# MotherBoard.net
KiCad netlist of a schematic drawn in EAGLE
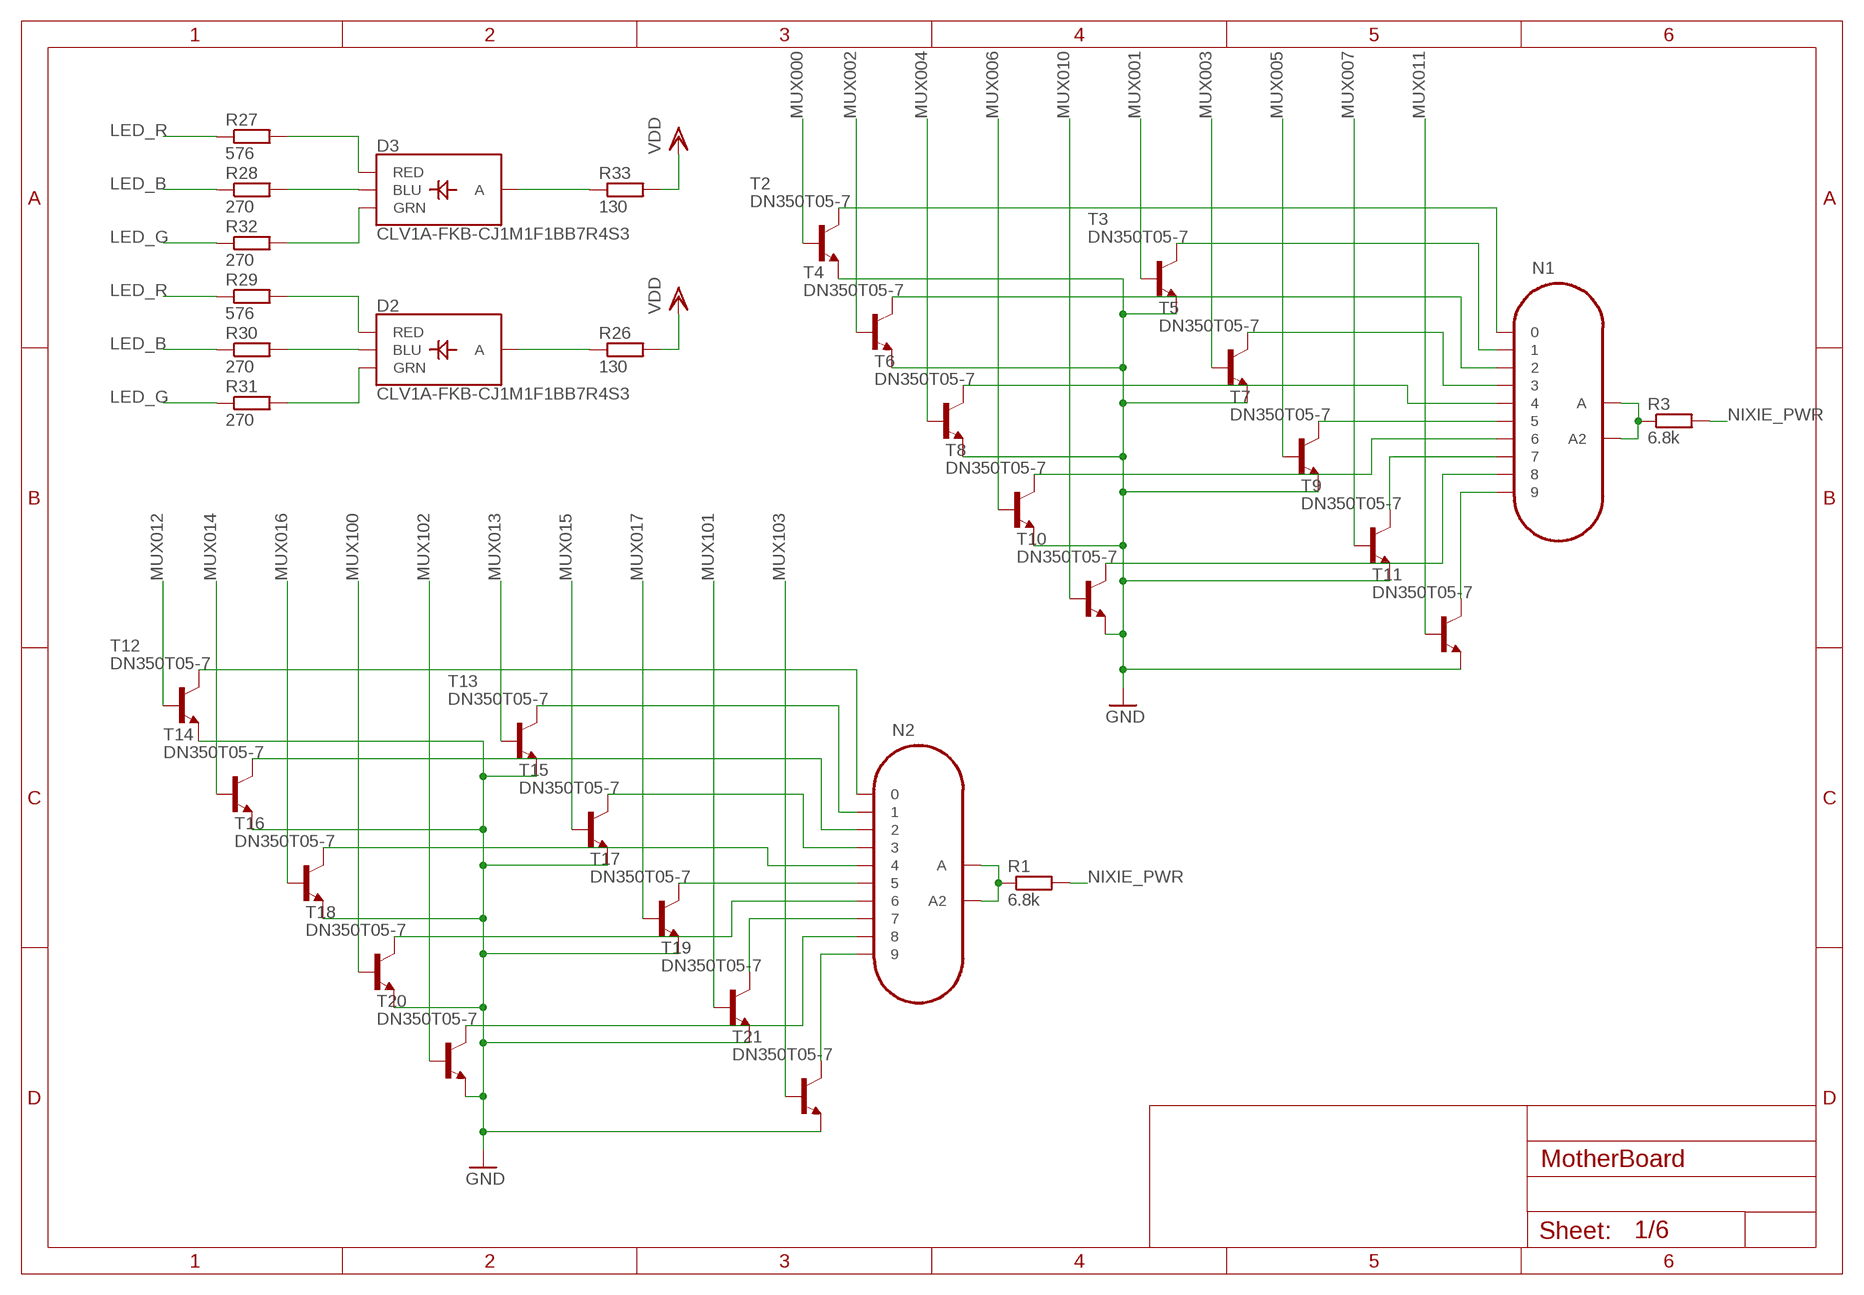
[diagram p0: schematic, sheet 1]
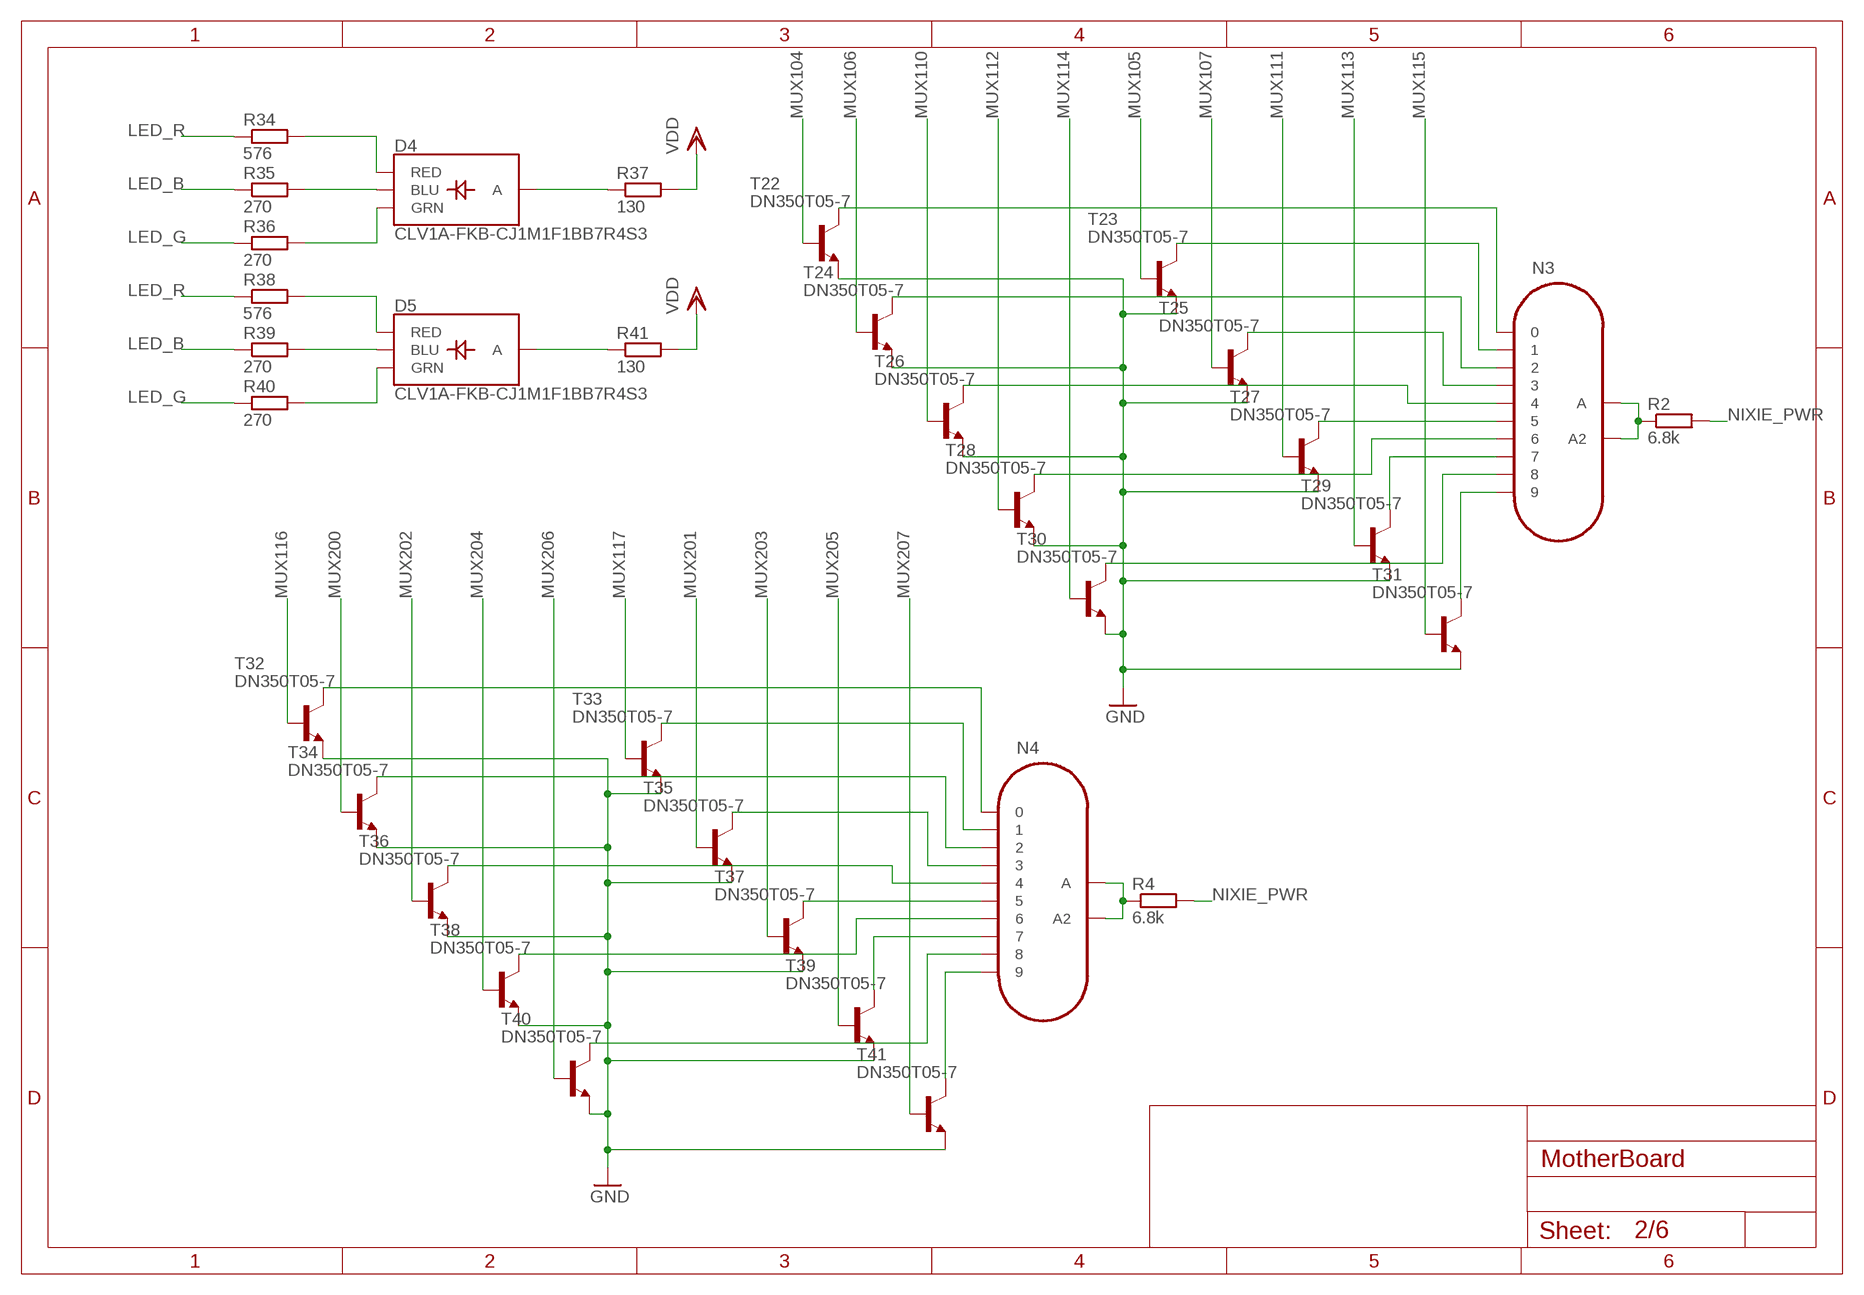
[diagram p1: schematic, sheet 2]
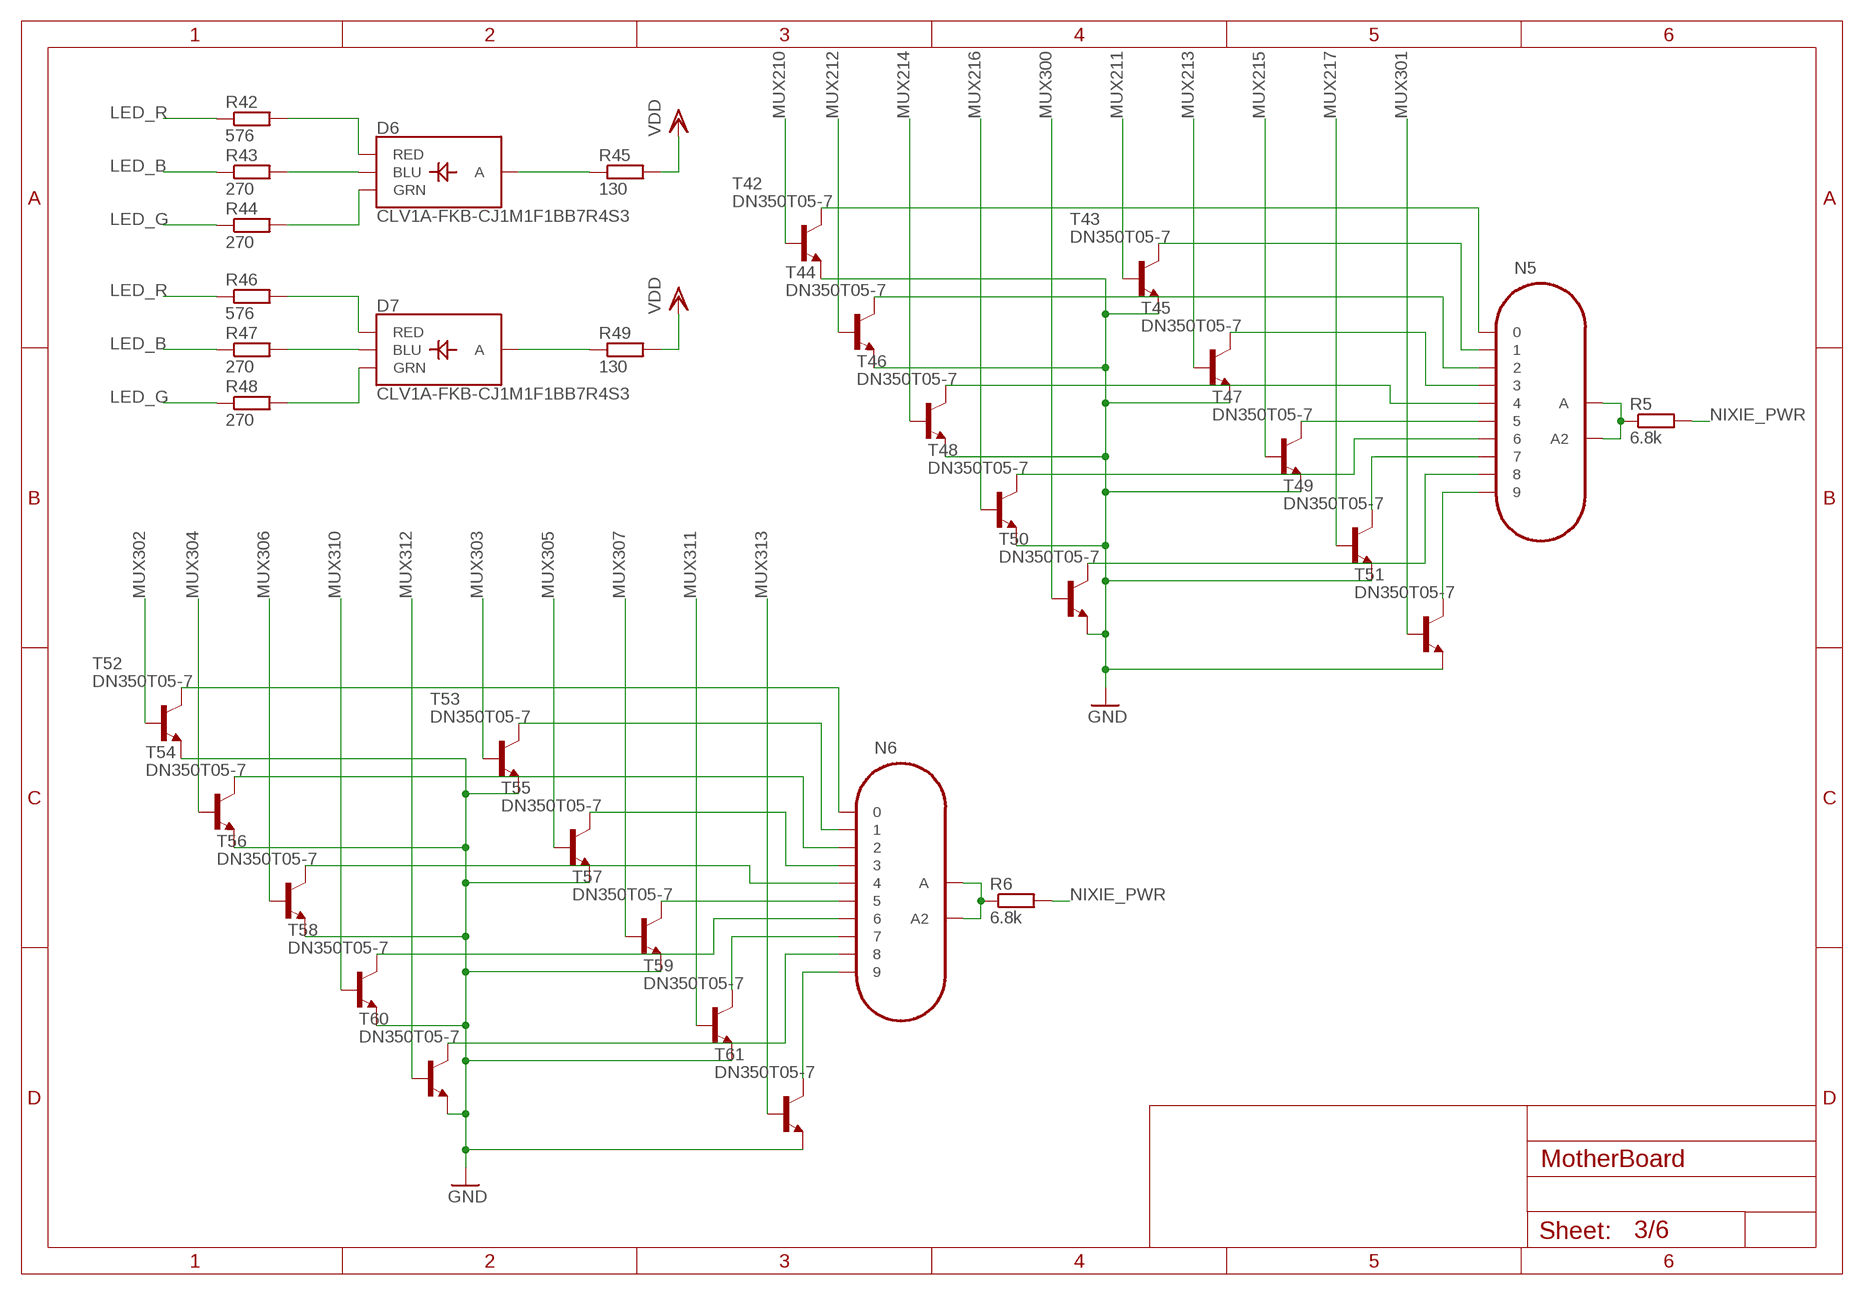
[diagram p2: schematic, sheet 3]
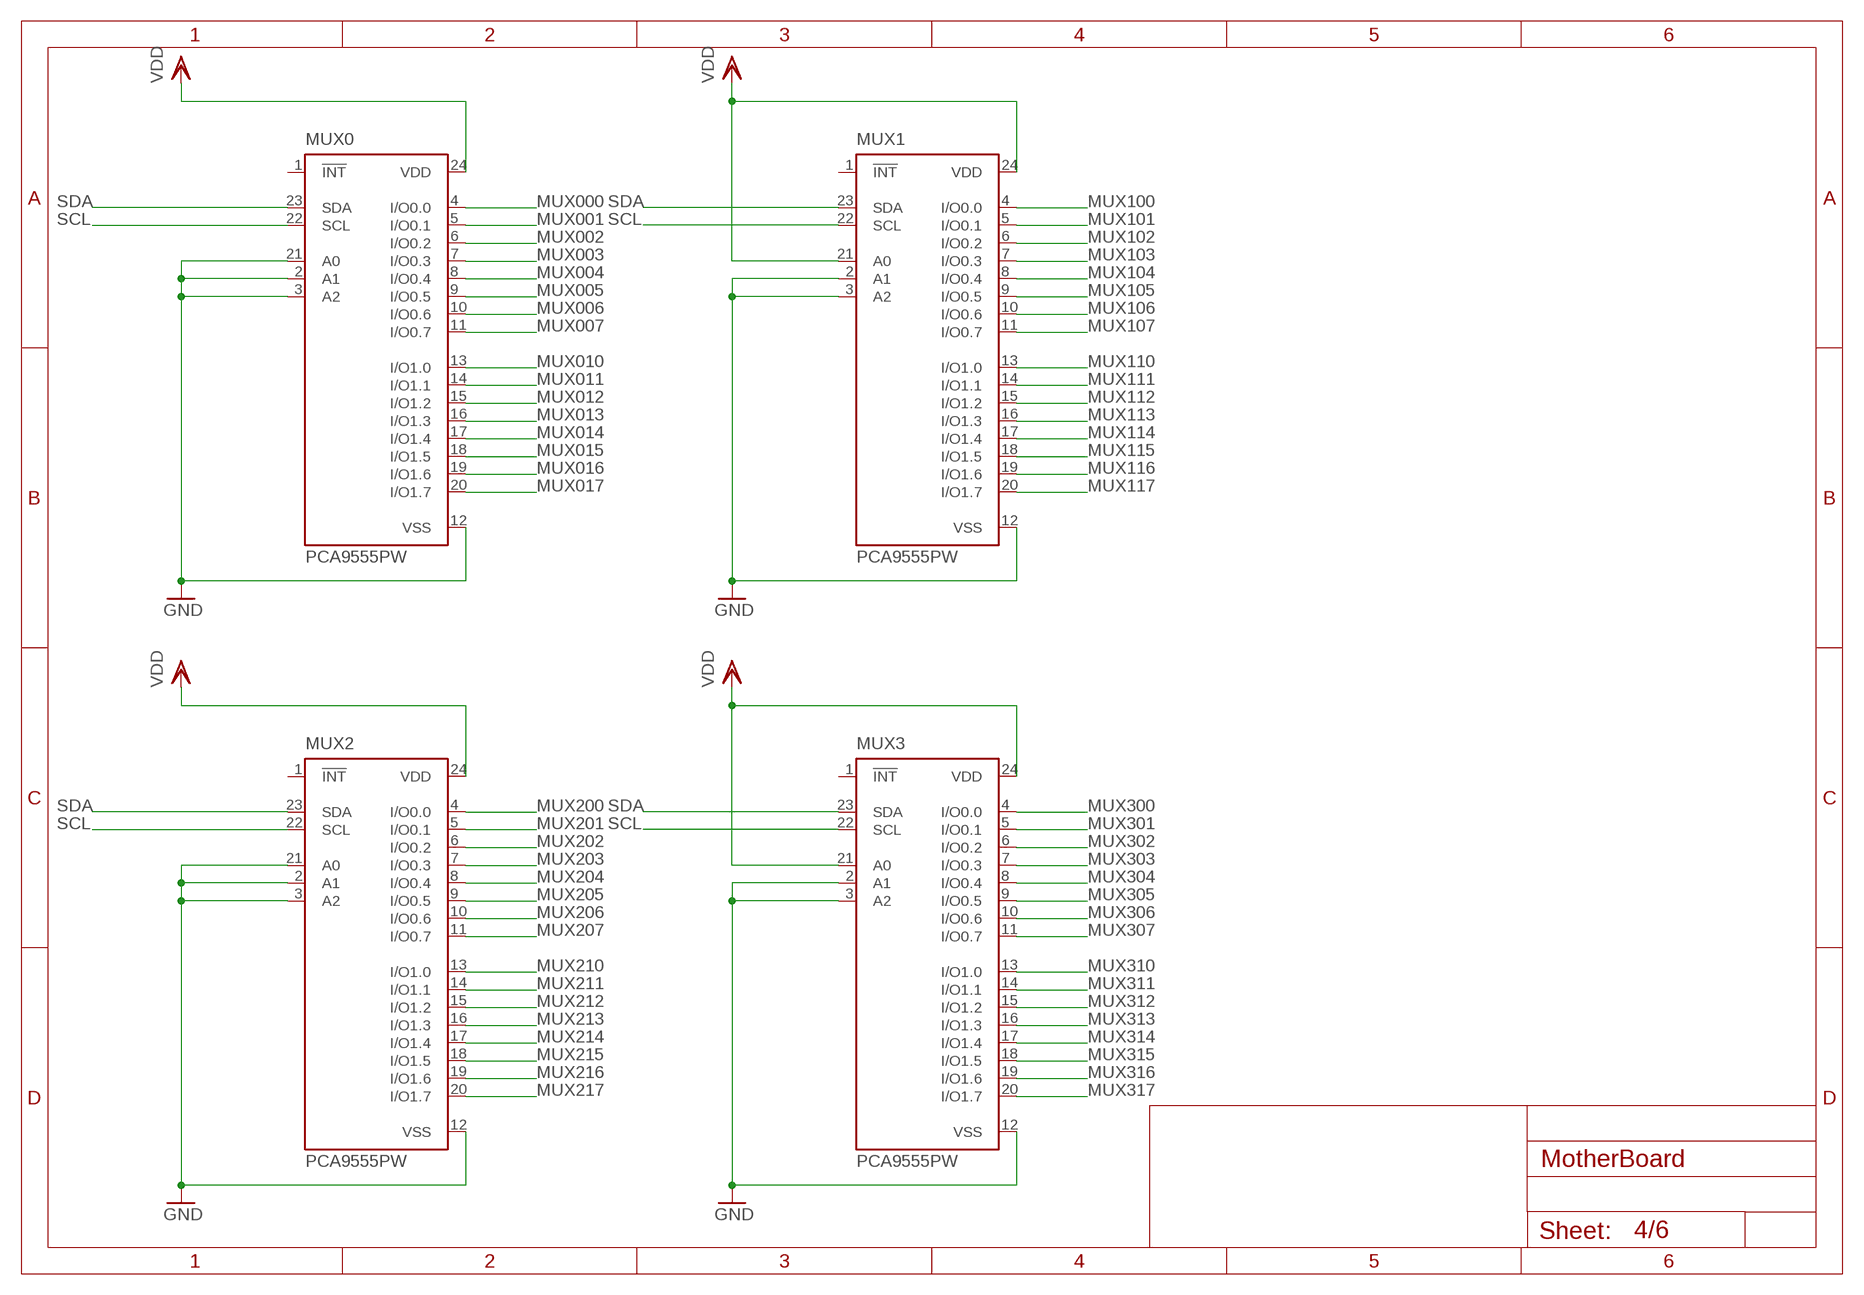
[diagram p3: schematic, sheet 4]
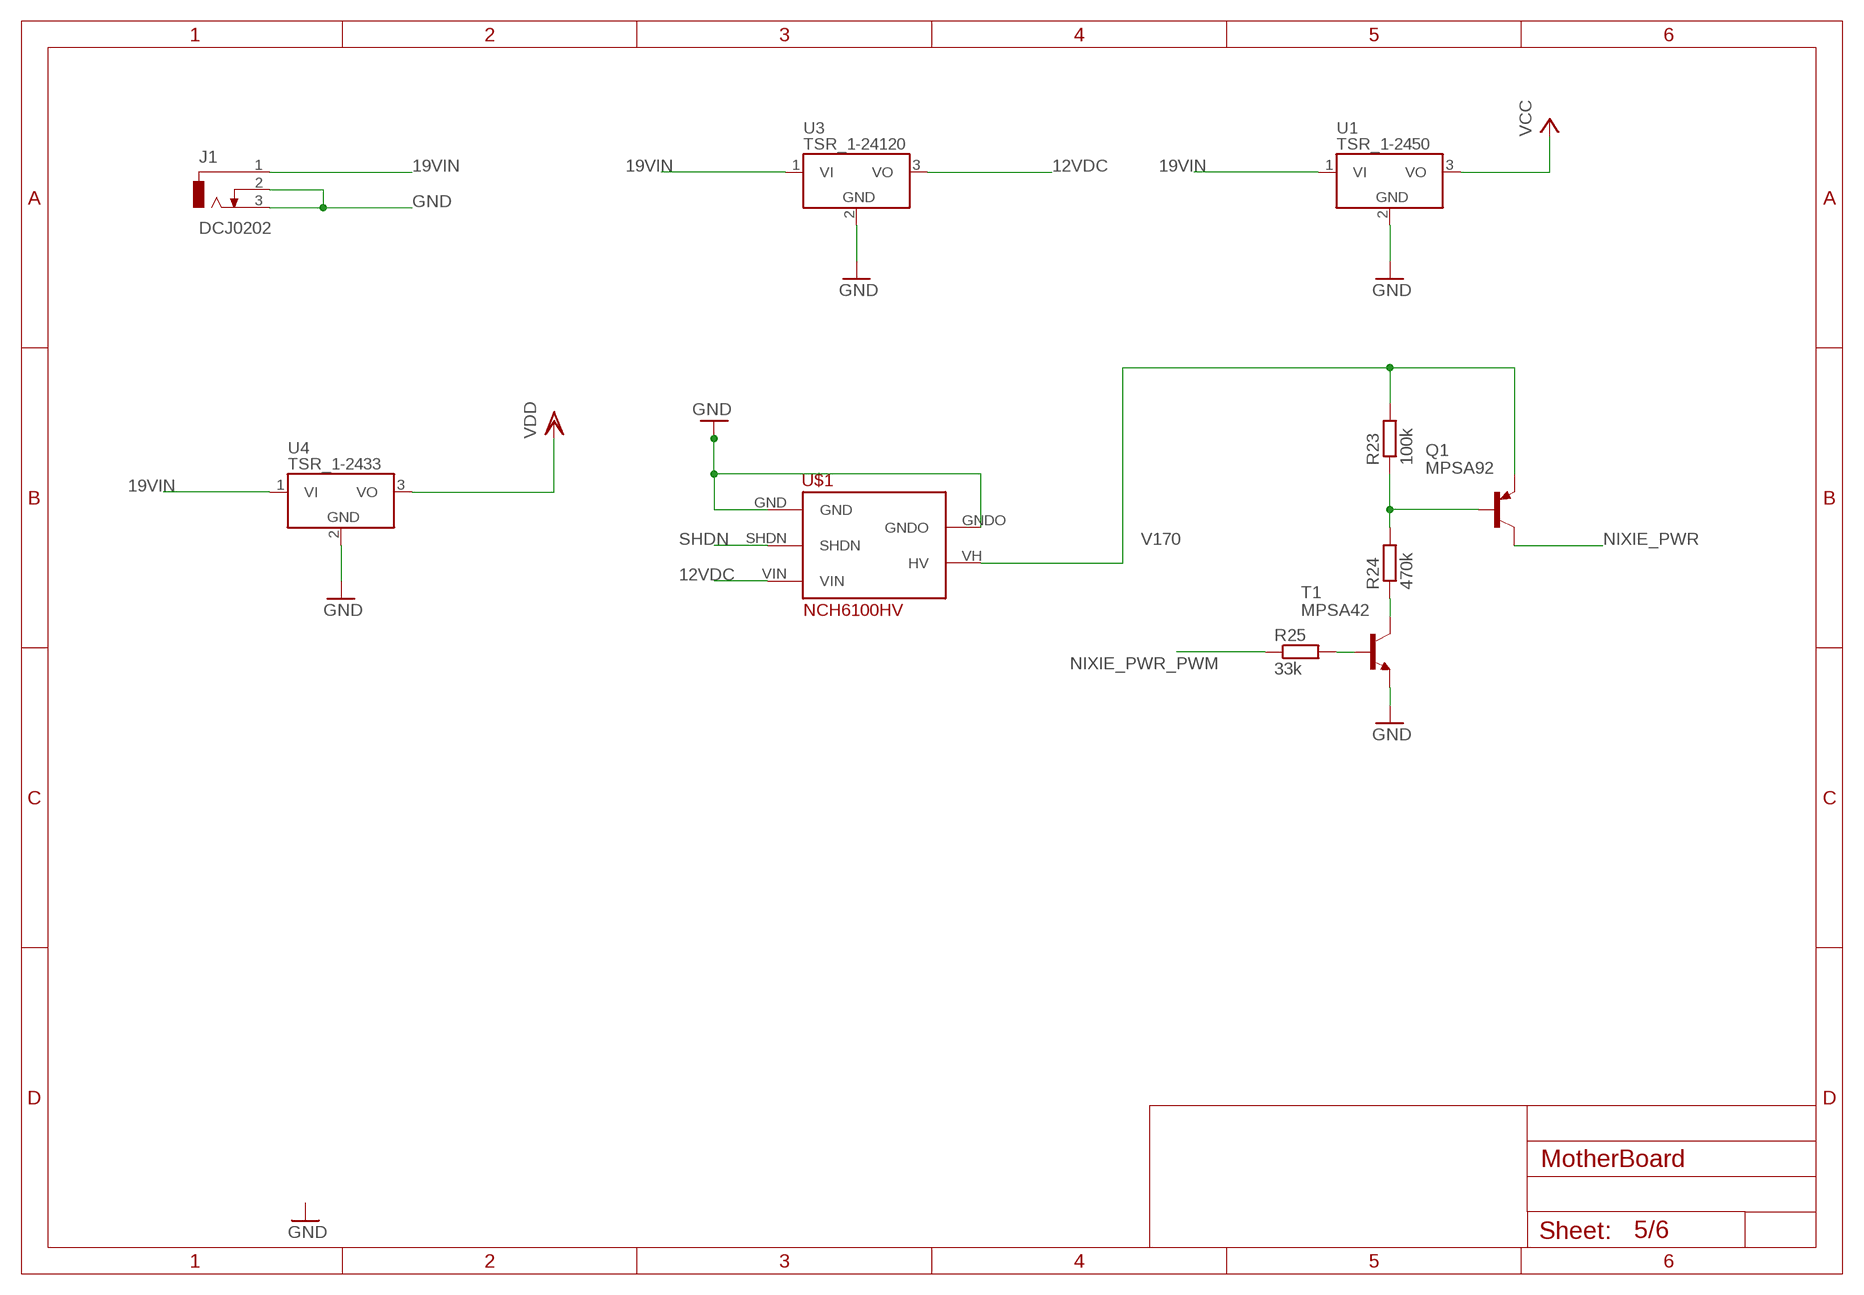
[diagram p4: schematic, sheet 5]
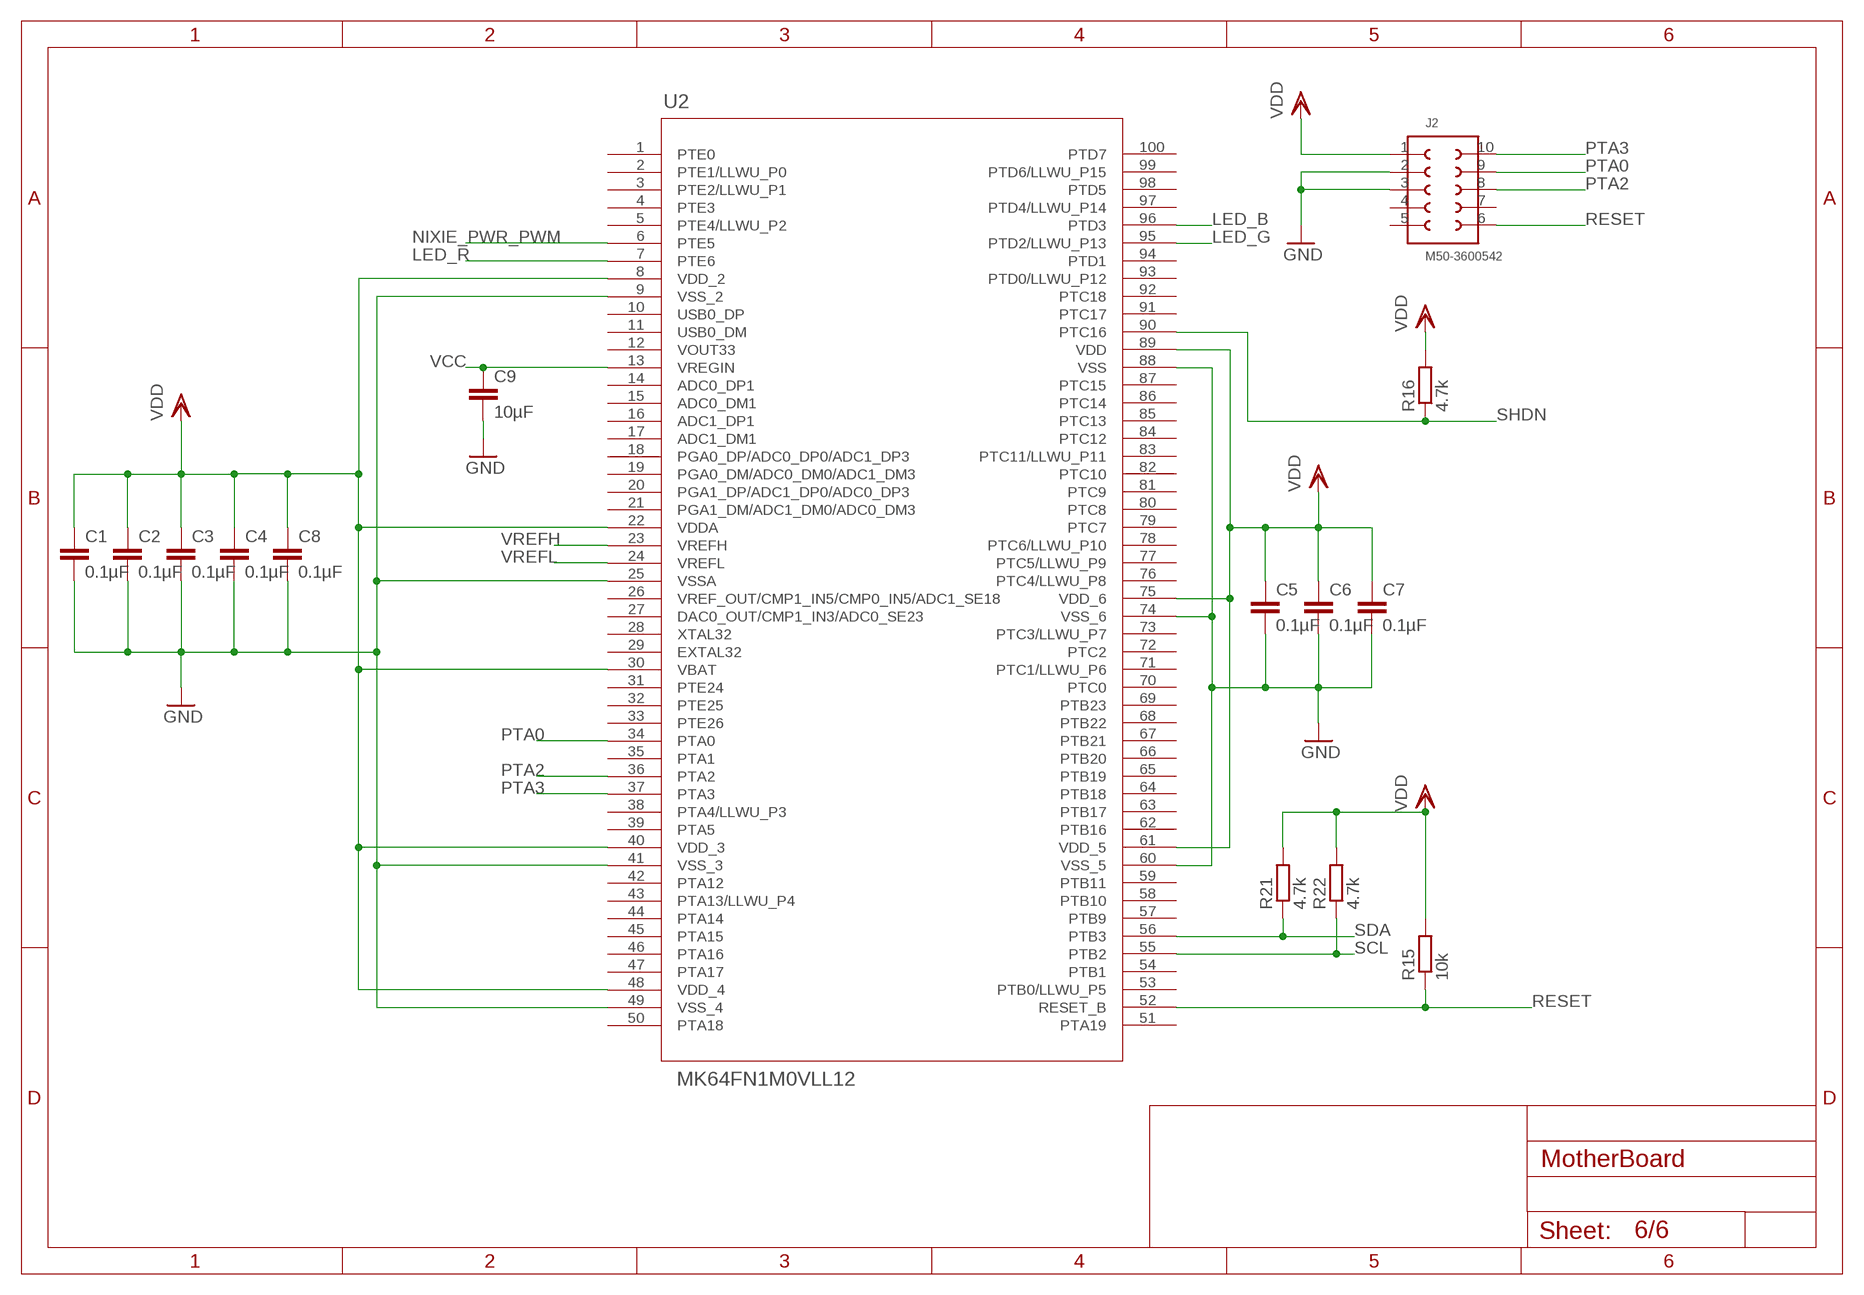
[diagram p5: schematic, sheet 6]

(export (version "E")
  (design (tool "Eeschema 10.0.6"))
  (components
    (comp (ref "C1")
      (value "0.1µF")
      (footprint "eagle-import:C0603")
      (libsource (lib "eagle-import") (part "C-EUC0603"))
    )
    (comp (ref "C2")
      (value "0.1µF")
      (footprint "eagle-import:C0603")
      (libsource (lib "eagle-import") (part "C-EUC0603"))
    )
    (comp (ref "C3")
      (value "0.1µF")
      (footprint "eagle-import:C0603")
      (libsource (lib "eagle-import") (part "C-EUC0603"))
    )
    (comp (ref "C4")
      (value "0.1µF")
      (footprint "eagle-import:C0603")
      (libsource (lib "eagle-import") (part "C-EUC0603"))
    )
    (comp (ref "C5")
      (value "0.1µF")
      (footprint "eagle-import:C0603")
      (libsource (lib "eagle-import") (part "C-EUC0603"))
    )
    (comp (ref "C6")
      (value "0.1µF")
      (footprint "eagle-import:C0603")
      (libsource (lib "eagle-import") (part "C-EUC0603"))
    )
    (comp (ref "C7")
      (value "0.1µF")
      (footprint "eagle-import:C0603")
      (libsource (lib "eagle-import") (part "C-EUC0603"))
    )
    (comp (ref "C8")
      (value "0.1µF")
      (footprint "eagle-import:C0603")
      (libsource (lib "eagle-import") (part "C-EUC0603"))
    )
    (comp (ref "C9")
      (value "10µF")
      (footprint "eagle-import:C0603")
      (libsource (lib "eagle-import") (part "C-EUC0603"))
    )
    (comp (ref "J2")
      (value "M50-3600542")
      (footprint "eagle-import:621X1021021")
      (libsource (lib "eagle-import") (part "621X1021021"))
    )
    (comp (ref "R15")
      (value "10k")
      (footprint "eagle-import:R0603")
      (libsource (lib "eagle-import") (part "R-EU_R0603"))
    )
    (comp (ref "R16")
      (value "4.7k")
      (footprint "eagle-import:R0603")
      (libsource (lib "eagle-import") (part "R-EU_R0603"))
    )
    (comp (ref "R21")
      (value "4.7k")
      (footprint "eagle-import:R0603")
      (libsource (lib "eagle-import") (part "R-EU_R0603"))
    )
    (comp (ref "R22")
      (value "4.7k")
      (footprint "eagle-import:R0603")
      (libsource (lib "eagle-import") (part "R-EU_R0603"))
    )
    (comp (ref "U2")
      (value "MK64FN1M0VLL12")
      (footprint "eagle-import:LQFP-100_14X14X1.7")
      (fields (field (name "MANUFACTURER_PART_NUMBER") "mk64fn1m0vll12"))
      (libsource (lib "eagle-import") (part "MK64FN1M0VLL12"))
    )
    (comp (ref "D4")
      (value "CLV1A-FKB-CJ1M1F1BB7R4S3")
      (footprint "eagle-import:P-LCC-4-3")
      (libsource (lib "eagle-import") (part "LED-RGB-CAPLCC"))
    )
    (comp (ref "D5")
      (value "CLV1A-FKB-CJ1M1F1BB7R4S3")
      (footprint "eagle-import:P-LCC-4-3")
      (libsource (lib "eagle-import") (part "LED-RGB-CAPLCC"))
    )
    (comp (ref "N3")
      (value "IN-18")
      (footprint "eagle-import:IN-18")
      (libsource (lib "eagle-import") (part "IN-18"))
    )
    (comp (ref "N4")
      (value "IN-18")
      (footprint "eagle-import:IN-18")
      (libsource (lib "eagle-import") (part "IN-18"))
    )
    (comp (ref "R2")
      (value "6.8k")
      (footprint "eagle-import:R0603")
      (libsource (lib "eagle-import") (part "R-EU_R0603"))
    )
    (comp (ref "R4")
      (value "6.8k")
      (footprint "eagle-import:R0603")
      (libsource (lib "eagle-import") (part "R-EU_R0603"))
    )
    (comp (ref "R34")
      (value "576")
      (footprint "eagle-import:R0603")
      (libsource (lib "eagle-import") (part "R-EU_R0603"))
    )
    (comp (ref "R35")
      (value "270")
      (footprint "eagle-import:R0603")
      (libsource (lib "eagle-import") (part "R-EU_R0603"))
    )
    (comp (ref "R36")
      (value "270")
      (footprint "eagle-import:R0603")
      (libsource (lib "eagle-import") (part "R-EU_R0603"))
    )
    (comp (ref "R37")
      (value "130")
      (footprint "eagle-import:R0603")
      (libsource (lib "eagle-import") (part "R-EU_R0603"))
    )
    (comp (ref "R38")
      (value "576")
      (footprint "eagle-import:R0603")
      (libsource (lib "eagle-import") (part "R-EU_R0603"))
    )
    (comp (ref "R39")
      (value "270")
      (footprint "eagle-import:R0603")
      (libsource (lib "eagle-import") (part "R-EU_R0603"))
    )
    (comp (ref "R40")
      (value "270")
      (footprint "eagle-import:R0603")
      (libsource (lib "eagle-import") (part "R-EU_R0603"))
    )
    (comp (ref "R41")
      (value "130")
      (footprint "eagle-import:R0603")
      (libsource (lib "eagle-import") (part "R-EU_R0603"))
    )
    (comp (ref "T22")
      (value "DN350T05-7")
      (footprint "eagle-import:SOT23-EBC")
      (libsource (lib "eagle-import") (part "-NPN-SOT23-EBC"))
    )
    (comp (ref "T23")
      (value "DN350T05-7")
      (footprint "eagle-import:SOT23-EBC")
      (libsource (lib "eagle-import") (part "-NPN-SOT23-EBC"))
    )
    (comp (ref "T24")
      (value "DN350T05-7")
      (footprint "eagle-import:SOT23-EBC")
      (libsource (lib "eagle-import") (part "-NPN-SOT23-EBC"))
    )
    (comp (ref "T25")
      (value "DN350T05-7")
      (footprint "eagle-import:SOT23-EBC")
      (libsource (lib "eagle-import") (part "-NPN-SOT23-EBC"))
    )
    (comp (ref "T26")
      (value "DN350T05-7")
      (footprint "eagle-import:SOT23-EBC")
      (libsource (lib "eagle-import") (part "-NPN-SOT23-EBC"))
    )
    (comp (ref "T27")
      (value "DN350T05-7")
      (footprint "eagle-import:SOT23-EBC")
      (libsource (lib "eagle-import") (part "-NPN-SOT23-EBC"))
    )
    (comp (ref "T28")
      (value "DN350T05-7")
      (footprint "eagle-import:SOT23-EBC")
      (libsource (lib "eagle-import") (part "-NPN-SOT23-EBC"))
    )
    (comp (ref "T29")
      (value "DN350T05-7")
      (footprint "eagle-import:SOT23-EBC")
      (libsource (lib "eagle-import") (part "-NPN-SOT23-EBC"))
    )
    (comp (ref "T30")
      (value "DN350T05-7")
      (footprint "eagle-import:SOT23-EBC")
      (libsource (lib "eagle-import") (part "-NPN-SOT23-EBC"))
    )
    (comp (ref "T31")
      (value "DN350T05-7")
      (footprint "eagle-import:SOT23-EBC")
      (libsource (lib "eagle-import") (part "-NPN-SOT23-EBC"))
    )
    (comp (ref "T32")
      (value "DN350T05-7")
      (footprint "eagle-import:SOT23-EBC")
      (libsource (lib "eagle-import") (part "-NPN-SOT23-EBC"))
    )
    (comp (ref "T33")
      (value "DN350T05-7")
      (footprint "eagle-import:SOT23-EBC")
      (libsource (lib "eagle-import") (part "-NPN-SOT23-EBC"))
    )
    (comp (ref "T34")
      (value "DN350T05-7")
      (footprint "eagle-import:SOT23-EBC")
      (libsource (lib "eagle-import") (part "-NPN-SOT23-EBC"))
    )
    (comp (ref "T35")
      (value "DN350T05-7")
      (footprint "eagle-import:SOT23-EBC")
      (libsource (lib "eagle-import") (part "-NPN-SOT23-EBC"))
    )
    (comp (ref "T36")
      (value "DN350T05-7")
      (footprint "eagle-import:SOT23-EBC")
      (libsource (lib "eagle-import") (part "-NPN-SOT23-EBC"))
    )
    (comp (ref "T37")
      (value "DN350T05-7")
      (footprint "eagle-import:SOT23-EBC")
      (libsource (lib "eagle-import") (part "-NPN-SOT23-EBC"))
    )
    (comp (ref "T38")
      (value "DN350T05-7")
      (footprint "eagle-import:SOT23-EBC")
      (libsource (lib "eagle-import") (part "-NPN-SOT23-EBC"))
    )
    (comp (ref "T39")
      (value "DN350T05-7")
      (footprint "eagle-import:SOT23-EBC")
      (libsource (lib "eagle-import") (part "-NPN-SOT23-EBC"))
    )
    (comp (ref "T40")
      (value "DN350T05-7")
      (footprint "eagle-import:SOT23-EBC")
      (libsource (lib "eagle-import") (part "-NPN-SOT23-EBC"))
    )
    (comp (ref "T41")
      (value "DN350T05-7")
      (footprint "eagle-import:SOT23-EBC")
      (libsource (lib "eagle-import") (part "-NPN-SOT23-EBC"))
    )
    (comp (ref "D2")
      (value "CLV1A-FKB-CJ1M1F1BB7R4S3")
      (footprint "eagle-import:P-LCC-4-3")
      (libsource (lib "eagle-import") (part "LED-RGB-CAPLCC"))
    )
    (comp (ref "D3")
      (value "CLV1A-FKB-CJ1M1F1BB7R4S3")
      (footprint "eagle-import:P-LCC-4-3")
      (libsource (lib "eagle-import") (part "LED-RGB-CAPLCC"))
    )
    (comp (ref "N1")
      (value "IN-18")
      (footprint "eagle-import:IN-18")
      (libsource (lib "eagle-import") (part "IN-18"))
    )
    (comp (ref "N2")
      (value "IN-18")
      (footprint "eagle-import:IN-18")
      (libsource (lib "eagle-import") (part "IN-18"))
    )
    (comp (ref "R1")
      (value "6.8k")
      (footprint "eagle-import:R0603")
      (libsource (lib "eagle-import") (part "R-EU_R0603"))
    )
    (comp (ref "R3")
      (value "6.8k")
      (footprint "eagle-import:R0603")
      (libsource (lib "eagle-import") (part "R-EU_R0603"))
    )
    (comp (ref "R26")
      (value "130")
      (footprint "eagle-import:R0603")
      (libsource (lib "eagle-import") (part "R-EU_R0603"))
    )
    (comp (ref "R27")
      (value "576")
      (footprint "eagle-import:R0603")
      (libsource (lib "eagle-import") (part "R-EU_R0603"))
    )
    (comp (ref "R28")
      (value "270")
      (footprint "eagle-import:R0603")
      (libsource (lib "eagle-import") (part "R-EU_R0603"))
    )
    (comp (ref "R29")
      (value "576")
      (footprint "eagle-import:R0603")
      (libsource (lib "eagle-import") (part "R-EU_R0603"))
    )
    (comp (ref "R30")
      (value "270")
      (footprint "eagle-import:R0603")
      (libsource (lib "eagle-import") (part "R-EU_R0603"))
    )
    (comp (ref "R31")
      (value "270")
      (footprint "eagle-import:R0603")
      (libsource (lib "eagle-import") (part "R-EU_R0603"))
    )
    (comp (ref "R32")
      (value "270")
      (footprint "eagle-import:R0603")
      (libsource (lib "eagle-import") (part "R-EU_R0603"))
    )
    (comp (ref "R33")
      (value "130")
      (footprint "eagle-import:R0603")
      (libsource (lib "eagle-import") (part "R-EU_R0603"))
    )
    (comp (ref "T2")
      (value "DN350T05-7")
      (footprint "eagle-import:SOT23-EBC")
      (libsource (lib "eagle-import") (part "-NPN-SOT23-EBC"))
    )
    (comp (ref "T3")
      (value "DN350T05-7")
      (footprint "eagle-import:SOT23-EBC")
      (libsource (lib "eagle-import") (part "-NPN-SOT23-EBC"))
    )
    (comp (ref "T4")
      (value "DN350T05-7")
      (footprint "eagle-import:SOT23-EBC")
      (libsource (lib "eagle-import") (part "-NPN-SOT23-EBC"))
    )
    (comp (ref "T5")
      (value "DN350T05-7")
      (footprint "eagle-import:SOT23-EBC")
      (libsource (lib "eagle-import") (part "-NPN-SOT23-EBC"))
    )
    (comp (ref "T6")
      (value "DN350T05-7")
      (footprint "eagle-import:SOT23-EBC")
      (libsource (lib "eagle-import") (part "-NPN-SOT23-EBC"))
    )
    (comp (ref "T7")
      (value "DN350T05-7")
      (footprint "eagle-import:SOT23-EBC")
      (libsource (lib "eagle-import") (part "-NPN-SOT23-EBC"))
    )
    (comp (ref "T8")
      (value "DN350T05-7")
      (footprint "eagle-import:SOT23-EBC")
      (libsource (lib "eagle-import") (part "-NPN-SOT23-EBC"))
    )
    (comp (ref "T9")
      (value "DN350T05-7")
      (footprint "eagle-import:SOT23-EBC")
      (libsource (lib "eagle-import") (part "-NPN-SOT23-EBC"))
    )
    (comp (ref "T10")
      (value "DN350T05-7")
      (footprint "eagle-import:SOT23-EBC")
      (libsource (lib "eagle-import") (part "-NPN-SOT23-EBC"))
    )
    (comp (ref "T11")
      (value "DN350T05-7")
      (footprint "eagle-import:SOT23-EBC")
      (libsource (lib "eagle-import") (part "-NPN-SOT23-EBC"))
    )
    (comp (ref "T12")
      (value "DN350T05-7")
      (footprint "eagle-import:SOT23-EBC")
      (libsource (lib "eagle-import") (part "-NPN-SOT23-EBC"))
    )
    (comp (ref "T13")
      (value "DN350T05-7")
      (footprint "eagle-import:SOT23-EBC")
      (libsource (lib "eagle-import") (part "-NPN-SOT23-EBC"))
    )
    (comp (ref "T14")
      (value "DN350T05-7")
      (footprint "eagle-import:SOT23-EBC")
      (libsource (lib "eagle-import") (part "-NPN-SOT23-EBC"))
    )
    (comp (ref "T15")
      (value "DN350T05-7")
      (footprint "eagle-import:SOT23-EBC")
      (libsource (lib "eagle-import") (part "-NPN-SOT23-EBC"))
    )
    (comp (ref "T16")
      (value "DN350T05-7")
      (footprint "eagle-import:SOT23-EBC")
      (libsource (lib "eagle-import") (part "-NPN-SOT23-EBC"))
    )
    (comp (ref "T17")
      (value "DN350T05-7")
      (footprint "eagle-import:SOT23-EBC")
      (libsource (lib "eagle-import") (part "-NPN-SOT23-EBC"))
    )
    (comp (ref "T18")
      (value "DN350T05-7")
      (footprint "eagle-import:SOT23-EBC")
      (libsource (lib "eagle-import") (part "-NPN-SOT23-EBC"))
    )
    (comp (ref "T19")
      (value "DN350T05-7")
      (footprint "eagle-import:SOT23-EBC")
      (libsource (lib "eagle-import") (part "-NPN-SOT23-EBC"))
    )
    (comp (ref "T20")
      (value "DN350T05-7")
      (footprint "eagle-import:SOT23-EBC")
      (libsource (lib "eagle-import") (part "-NPN-SOT23-EBC"))
    )
    (comp (ref "T21")
      (value "DN350T05-7")
      (footprint "eagle-import:SOT23-EBC")
      (libsource (lib "eagle-import") (part "-NPN-SOT23-EBC"))
    )
    (comp (ref "MUX0")
      (value "PCA9555PW")
      (footprint "eagle-import:TSSOP24")
      (libsource (lib "eagle-import") (part "PCA9555PW"))
    )
    (comp (ref "MUX1")
      (value "PCA9555PW")
      (footprint "eagle-import:TSSOP24")
      (libsource (lib "eagle-import") (part "PCA9555PW"))
    )
    (comp (ref "MUX2")
      (value "PCA9555PW")
      (footprint "eagle-import:TSSOP24")
      (libsource (lib "eagle-import") (part "PCA9555PW"))
    )
    (comp (ref "MUX3")
      (value "PCA9555PW")
      (footprint "eagle-import:TSSOP24")
      (libsource (lib "eagle-import") (part "PCA9555PW"))
    )
    (comp (ref "D6")
      (value "CLV1A-FKB-CJ1M1F1BB7R4S3")
      (footprint "eagle-import:P-LCC-4-3")
      (libsource (lib "eagle-import") (part "LED-RGB-CAPLCC"))
    )
    (comp (ref "D7")
      (value "CLV1A-FKB-CJ1M1F1BB7R4S3")
      (footprint "eagle-import:P-LCC-4-3")
      (libsource (lib "eagle-import") (part "LED-RGB-CAPLCC"))
    )
    (comp (ref "N5")
      (value "IN-18")
      (footprint "eagle-import:IN-18")
      (libsource (lib "eagle-import") (part "IN-18"))
    )
    (comp (ref "N6")
      (value "IN-18")
      (footprint "eagle-import:IN-18")
      (libsource (lib "eagle-import") (part "IN-18"))
    )
    (comp (ref "R5")
      (value "6.8k")
      (footprint "eagle-import:R0603")
      (libsource (lib "eagle-import") (part "R-EU_R0603"))
    )
    (comp (ref "R6")
      (value "6.8k")
      (footprint "eagle-import:R0603")
      (libsource (lib "eagle-import") (part "R-EU_R0603"))
    )
    (comp (ref "R42")
      (value "576")
      (footprint "eagle-import:R0603")
      (libsource (lib "eagle-import") (part "R-EU_R0603"))
    )
    (comp (ref "R43")
      (value "270")
      (footprint "eagle-import:R0603")
      (libsource (lib "eagle-import") (part "R-EU_R0603"))
    )
    (comp (ref "R44")
      (value "270")
      (footprint "eagle-import:R0603")
      (libsource (lib "eagle-import") (part "R-EU_R0603"))
    )
    (comp (ref "R45")
      (value "130")
      (footprint "eagle-import:R0603")
      (libsource (lib "eagle-import") (part "R-EU_R0603"))
    )
    (comp (ref "R46")
      (value "576")
      (footprint "eagle-import:R0603")
      (libsource (lib "eagle-import") (part "R-EU_R0603"))
    )
    (comp (ref "R47")
      (value "270")
      (footprint "eagle-import:R0603")
      (libsource (lib "eagle-import") (part "R-EU_R0603"))
    )
    (comp (ref "R48")
      (value "270")
      (footprint "eagle-import:R0603")
      (libsource (lib "eagle-import") (part "R-EU_R0603"))
    )
    (comp (ref "R49")
      (value "130")
      (footprint "eagle-import:R0603")
      (libsource (lib "eagle-import") (part "R-EU_R0603"))
    )
    (comp (ref "T42")
      (value "DN350T05-7")
      (footprint "eagle-import:SOT23-EBC")
      (libsource (lib "eagle-import") (part "-NPN-SOT23-EBC"))
    )
    (comp (ref "T43")
      (value "DN350T05-7")
      (footprint "eagle-import:SOT23-EBC")
      (libsource (lib "eagle-import") (part "-NPN-SOT23-EBC"))
    )
    (comp (ref "T44")
      (value "DN350T05-7")
      (footprint "eagle-import:SOT23-EBC")
      (libsource (lib "eagle-import") (part "-NPN-SOT23-EBC"))
    )
    (comp (ref "T45")
      (value "DN350T05-7")
      (footprint "eagle-import:SOT23-EBC")
      (libsource (lib "eagle-import") (part "-NPN-SOT23-EBC"))
    )
    (comp (ref "T46")
      (value "DN350T05-7")
      (footprint "eagle-import:SOT23-EBC")
      (libsource (lib "eagle-import") (part "-NPN-SOT23-EBC"))
    )
    (comp (ref "T47")
      (value "DN350T05-7")
      (footprint "eagle-import:SOT23-EBC")
      (libsource (lib "eagle-import") (part "-NPN-SOT23-EBC"))
    )
    (comp (ref "T48")
      (value "DN350T05-7")
      (footprint "eagle-import:SOT23-EBC")
      (libsource (lib "eagle-import") (part "-NPN-SOT23-EBC"))
    )
    (comp (ref "T49")
      (value "DN350T05-7")
      (footprint "eagle-import:SOT23-EBC")
      (libsource (lib "eagle-import") (part "-NPN-SOT23-EBC"))
    )
    (comp (ref "T50")
      (value "DN350T05-7")
      (footprint "eagle-import:SOT23-EBC")
      (libsource (lib "eagle-import") (part "-NPN-SOT23-EBC"))
    )
    (comp (ref "T51")
      (value "DN350T05-7")
      (footprint "eagle-import:SOT23-EBC")
      (libsource (lib "eagle-import") (part "-NPN-SOT23-EBC"))
    )
    (comp (ref "T52")
      (value "DN350T05-7")
      (footprint "eagle-import:SOT23-EBC")
      (libsource (lib "eagle-import") (part "-NPN-SOT23-EBC"))
    )
    (comp (ref "T53")
      (value "DN350T05-7")
      (footprint "eagle-import:SOT23-EBC")
      (libsource (lib "eagle-import") (part "-NPN-SOT23-EBC"))
    )
    (comp (ref "T54")
      (value "DN350T05-7")
      (footprint "eagle-import:SOT23-EBC")
      (libsource (lib "eagle-import") (part "-NPN-SOT23-EBC"))
    )
    (comp (ref "T55")
      (value "DN350T05-7")
      (footprint "eagle-import:SOT23-EBC")
      (libsource (lib "eagle-import") (part "-NPN-SOT23-EBC"))
    )
    (comp (ref "T56")
      (value "DN350T05-7")
      (footprint "eagle-import:SOT23-EBC")
      (libsource (lib "eagle-import") (part "-NPN-SOT23-EBC"))
    )
    (comp (ref "T57")
      (value "DN350T05-7")
      (footprint "eagle-import:SOT23-EBC")
      (libsource (lib "eagle-import") (part "-NPN-SOT23-EBC"))
    )
    (comp (ref "T58")
      (value "DN350T05-7")
      (footprint "eagle-import:SOT23-EBC")
      (libsource (lib "eagle-import") (part "-NPN-SOT23-EBC"))
    )
    (comp (ref "T59")
      (value "DN350T05-7")
      (footprint "eagle-import:SOT23-EBC")
      (libsource (lib "eagle-import") (part "-NPN-SOT23-EBC"))
    )
    (comp (ref "T60")
      (value "DN350T05-7")
      (footprint "eagle-import:SOT23-EBC")
      (libsource (lib "eagle-import") (part "-NPN-SOT23-EBC"))
    )
    (comp (ref "T61")
      (value "DN350T05-7")
      (footprint "eagle-import:SOT23-EBC")
      (libsource (lib "eagle-import") (part "-NPN-SOT23-EBC"))
    )
    (comp (ref "J1")
      (value "DCJ0202")
      (footprint "eagle-import:DCJ0202")
      (libsource (lib "eagle-import") (part "DCJ0202"))
    )
    (comp (ref "Q1")
      (value "MPSA92")
      (footprint "eagle-import:SOT23")
      (libsource (lib "eagle-import") (part "-?SOT23MMBTA56"))
    )
    (comp (ref "R23")
      (value "100k")
      (footprint "eagle-import:R0603")
      (libsource (lib "eagle-import") (part "R-EU_R0603"))
    )
    (comp (ref "R24")
      (value "470k")
      (footprint "eagle-import:R0603")
      (libsource (lib "eagle-import") (part "R-EU_R0603"))
    )
    (comp (ref "R25")
      (value "33k")
      (footprint "eagle-import:R0603")
      (libsource (lib "eagle-import") (part "R-EU_R0603"))
    )
    (comp (ref "T1")
      (value "MPSA42")
      (footprint "eagle-import:SOT23-BEC")
      (libsource (lib "eagle-import") (part "-NPN-SOT23-BECMMBTA42LT1"))
    )
    (comp (ref "U$1")
      (value "NCH6100HV")
      (footprint "eagle-import:NCH6100-STD")
      (libsource (lib "eagle-import") (part "NCH6100HV"))
    )
    (comp (ref "U1")
      (value "TSR_1-2450")
      (footprint "eagle-import:TSR-1")
      (libsource (lib "eagle-import") (part "TSR_1-2450"))
    )
    (comp (ref "U3")
      (value "TSR_1-24120")
      (footprint "eagle-import:TSR-1")
      (libsource (lib "eagle-import") (part "TSR_1-24120"))
    )
    (comp (ref "U4")
      (value "TSR_1-2433")
      (footprint "eagle-import:TSR-1")
      (libsource (lib "eagle-import") (part "TSR_1-2433"))
    )
  )
  (nets
    (net (code "1") (name "12VDC") (class "Default")
      (node (ref "U$1") (pin "VIN") (pinfunction "VIN_VIN") (pintype "bidirectional"))
      (node (ref "U3") (pin "3") (pinfunction "VO_3") (pintype "power_in"))
    )
    (net (code "2") (name "19VIN") (class "Default")
      (node (ref "J1") (pin "1") (pinfunction "1_1") (pintype "passive"))
      (node (ref "U1") (pin "1") (pinfunction "VI_1") (pintype "power_in"))
      (node (ref "U3") (pin "1") (pinfunction "VI_1") (pintype "power_in"))
      (node (ref "U4") (pin "1") (pinfunction "VI_1") (pintype "power_in"))
    )
    (net (code "3") (name "GND") (class "Default")
      (node (ref "C1") (pin "2") (pinfunction "2_2") (pintype "passive"))
      (node (ref "C2") (pin "2") (pinfunction "2_2") (pintype "passive"))
      (node (ref "C3") (pin "2") (pinfunction "2_2") (pintype "passive"))
      (node (ref "C4") (pin "2") (pinfunction "2_2") (pintype "passive"))
      (node (ref "C5") (pin "2") (pinfunction "2_2") (pintype "passive"))
      (node (ref "C6") (pin "2") (pinfunction "2_2") (pintype "passive"))
      (node (ref "C7") (pin "2") (pinfunction "2_2") (pintype "passive"))
      (node (ref "C8") (pin "2") (pinfunction "2_2") (pintype "passive"))
      (node (ref "C9") (pin "2") (pinfunction "2_2") (pintype "passive"))
      (node (ref "J1") (pin "2") (pinfunction "2_2") (pintype "passive"))
      (node (ref "J1") (pin "3") (pinfunction "3_3") (pintype "passive"))
      (node (ref "J2") (pin "2") (pinfunction "2_2") (pintype "passive"))
      (node (ref "J2") (pin "3") (pinfunction "3_3") (pintype "passive"))
      (node (ref "MUX0") (pin "12") (pinfunction "VSS_12") (pintype "power_in"))
      (node (ref "MUX0") (pin "2") (pinfunction "A1_2") (pintype "input"))
      (node (ref "MUX0") (pin "21") (pinfunction "A0_21") (pintype "input"))
      (node (ref "MUX0") (pin "3") (pinfunction "A2_3") (pintype "input"))
      (node (ref "MUX1") (pin "12") (pinfunction "VSS_12") (pintype "power_in"))
      (node (ref "MUX1") (pin "2") (pinfunction "A1_2") (pintype "input"))
      (node (ref "MUX1") (pin "3") (pinfunction "A2_3") (pintype "input"))
      (node (ref "MUX2") (pin "12") (pinfunction "VSS_12") (pintype "power_in"))
      (node (ref "MUX2") (pin "2") (pinfunction "A1_2") (pintype "input"))
      (node (ref "MUX2") (pin "21") (pinfunction "A0_21") (pintype "input"))
      (node (ref "MUX2") (pin "3") (pinfunction "A2_3") (pintype "input"))
      (node (ref "MUX3") (pin "12") (pinfunction "VSS_12") (pintype "power_in"))
      (node (ref "MUX3") (pin "2") (pinfunction "A1_2") (pintype "input"))
      (node (ref "MUX3") (pin "3") (pinfunction "A2_3") (pintype "input"))
      (node (ref "T1") (pin "E") (pinfunction "E_E") (pintype "passive"))
      (node (ref "T10") (pin "E") (pinfunction "E_E") (pintype "passive"))
      (node (ref "T11") (pin "E") (pinfunction "E_E") (pintype "passive"))
      (node (ref "T12") (pin "E") (pinfunction "E_E") (pintype "passive"))
      (node (ref "T13") (pin "E") (pinfunction "E_E") (pintype "passive"))
      (node (ref "T14") (pin "E") (pinfunction "E_E") (pintype "passive"))
      (node (ref "T15") (pin "E") (pinfunction "E_E") (pintype "passive"))
      (node (ref "T16") (pin "E") (pinfunction "E_E") (pintype "passive"))
      (node (ref "T17") (pin "E") (pinfunction "E_E") (pintype "passive"))
      (node (ref "T18") (pin "E") (pinfunction "E_E") (pintype "passive"))
      (node (ref "T19") (pin "E") (pinfunction "E_E") (pintype "passive"))
      (node (ref "T2") (pin "E") (pinfunction "E_E") (pintype "passive"))
      (node (ref "T20") (pin "E") (pinfunction "E_E") (pintype "passive"))
      (node (ref "T21") (pin "E") (pinfunction "E_E") (pintype "passive"))
      (node (ref "T22") (pin "E") (pinfunction "E_E") (pintype "passive"))
      (node (ref "T23") (pin "E") (pinfunction "E_E") (pintype "passive"))
      (node (ref "T24") (pin "E") (pinfunction "E_E") (pintype "passive"))
      (node (ref "T25") (pin "E") (pinfunction "E_E") (pintype "passive"))
      (node (ref "T26") (pin "E") (pinfunction "E_E") (pintype "passive"))
      (node (ref "T27") (pin "E") (pinfunction "E_E") (pintype "passive"))
      (node (ref "T28") (pin "E") (pinfunction "E_E") (pintype "passive"))
      (node (ref "T29") (pin "E") (pinfunction "E_E") (pintype "passive"))
      (node (ref "T3") (pin "E") (pinfunction "E_E") (pintype "passive"))
      (node (ref "T30") (pin "E") (pinfunction "E_E") (pintype "passive"))
      (node (ref "T31") (pin "E") (pinfunction "E_E") (pintype "passive"))
      (node (ref "T32") (pin "E") (pinfunction "E_E") (pintype "passive"))
      (node (ref "T33") (pin "E") (pinfunction "E_E") (pintype "passive"))
      (node (ref "T34") (pin "E") (pinfunction "E_E") (pintype "passive"))
      (node (ref "T35") (pin "E") (pinfunction "E_E") (pintype "passive"))
      (node (ref "T36") (pin "E") (pinfunction "E_E") (pintype "passive"))
      (node (ref "T37") (pin "E") (pinfunction "E_E") (pintype "passive"))
      (node (ref "T38") (pin "E") (pinfunction "E_E") (pintype "passive"))
      (node (ref "T39") (pin "E") (pinfunction "E_E") (pintype "passive"))
      (node (ref "T4") (pin "E") (pinfunction "E_E") (pintype "passive"))
      (node (ref "T40") (pin "E") (pinfunction "E_E") (pintype "passive"))
      (node (ref "T41") (pin "E") (pinfunction "E_E") (pintype "passive"))
      (node (ref "T42") (pin "E") (pinfunction "E_E") (pintype "passive"))
      (node (ref "T43") (pin "E") (pinfunction "E_E") (pintype "passive"))
      (node (ref "T44") (pin "E") (pinfunction "E_E") (pintype "passive"))
      (node (ref "T45") (pin "E") (pinfunction "E_E") (pintype "passive"))
      (node (ref "T46") (pin "E") (pinfunction "E_E") (pintype "passive"))
      (node (ref "T47") (pin "E") (pinfunction "E_E") (pintype "passive"))
      (node (ref "T48") (pin "E") (pinfunction "E_E") (pintype "passive"))
      (node (ref "T49") (pin "E") (pinfunction "E_E") (pintype "passive"))
      (node (ref "T5") (pin "E") (pinfunction "E_E") (pintype "passive"))
      (node (ref "T50") (pin "E") (pinfunction "E_E") (pintype "passive"))
      (node (ref "T51") (pin "E") (pinfunction "E_E") (pintype "passive"))
      (node (ref "T52") (pin "E") (pinfunction "E_E") (pintype "passive"))
      (node (ref "T53") (pin "E") (pinfunction "E_E") (pintype "passive"))
      (node (ref "T54") (pin "E") (pinfunction "E_E") (pintype "passive"))
      (node (ref "T55") (pin "E") (pinfunction "E_E") (pintype "passive"))
      (node (ref "T56") (pin "E") (pinfunction "E_E") (pintype "passive"))
      (node (ref "T57") (pin "E") (pinfunction "E_E") (pintype "passive"))
      (node (ref "T58") (pin "E") (pinfunction "E_E") (pintype "passive"))
      (node (ref "T59") (pin "E") (pinfunction "E_E") (pintype "passive"))
      (node (ref "T6") (pin "E") (pinfunction "E_E") (pintype "passive"))
      (node (ref "T60") (pin "E") (pinfunction "E_E") (pintype "passive"))
      (node (ref "T61") (pin "E") (pinfunction "E_E") (pintype "passive"))
      (node (ref "T7") (pin "E") (pinfunction "E_E") (pintype "passive"))
      (node (ref "T8") (pin "E") (pinfunction "E_E") (pintype "passive"))
      (node (ref "T9") (pin "E") (pinfunction "E_E") (pintype "passive"))
      (node (ref "U$1") (pin "GND") (pinfunction "GND_GND") (pintype "bidirectional"))
      (node (ref "U$1") (pin "GNDO") (pinfunction "GNDO_GNDO") (pintype "bidirectional"))
      (node (ref "U1") (pin "2") (pinfunction "GND_2") (pintype "power_in"))
      (node (ref "U2") (pin "25") (pinfunction "VSSA_25") (pintype "power_in"))
      (node (ref "U2") (pin "41") (pinfunction "VSS_3_41") (pintype "power_in"))
      (node (ref "U2") (pin "49") (pinfunction "VSS_4_49") (pintype "power_in"))
      (node (ref "U2") (pin "60") (pinfunction "VSS_5_60") (pintype "power_in"))
      (node (ref "U2") (pin "74") (pinfunction "VSS_6_74") (pintype "power_in"))
      (node (ref "U2") (pin "88") (pinfunction "VSS_88") (pintype "power_in"))
      (node (ref "U2") (pin "9") (pinfunction "VSS_2_9") (pintype "power_in"))
      (node (ref "U3") (pin "2") (pinfunction "GND_2") (pintype "power_in"))
      (node (ref "U4") (pin "2") (pinfunction "GND_2") (pintype "power_in"))
    )
    (net (code "4") (name "LED_B") (class "Default")
      (node (ref "R28") (pin "1") (pinfunction "1_1") (pintype "passive"))
      (node (ref "R30") (pin "1") (pinfunction "1_1") (pintype "passive"))
      (node (ref "R35") (pin "1") (pinfunction "1_1") (pintype "passive"))
      (node (ref "R39") (pin "1") (pinfunction "1_1") (pintype "passive"))
      (node (ref "R43") (pin "1") (pinfunction "1_1") (pintype "passive"))
      (node (ref "R47") (pin "1") (pinfunction "1_1") (pintype "passive"))
      (node (ref "U2") (pin "96") (pinfunction "PTD3_96") (pintype "bidirectional"))
    )
    (net (code "5") (name "LED_G") (class "Default")
      (node (ref "R31") (pin "1") (pinfunction "1_1") (pintype "passive"))
      (node (ref "R32") (pin "1") (pinfunction "1_1") (pintype "passive"))
      (node (ref "R36") (pin "1") (pinfunction "1_1") (pintype "passive"))
      (node (ref "R40") (pin "1") (pinfunction "1_1") (pintype "passive"))
      (node (ref "R44") (pin "1") (pinfunction "1_1") (pintype "passive"))
      (node (ref "R48") (pin "1") (pinfunction "1_1") (pintype "passive"))
      (node (ref "U2") (pin "95") (pinfunction "PTD2/LLWU_P13_95") (pintype "bidirectional"))
    )
    (net (code "6") (name "LED_R") (class "Default")
      (node (ref "R27") (pin "1") (pinfunction "1_1") (pintype "passive"))
      (node (ref "R29") (pin "1") (pinfunction "1_1") (pintype "passive"))
      (node (ref "R34") (pin "1") (pinfunction "1_1") (pintype "passive"))
      (node (ref "R38") (pin "1") (pinfunction "1_1") (pintype "passive"))
      (node (ref "R42") (pin "1") (pinfunction "1_1") (pintype "passive"))
      (node (ref "R46") (pin "1") (pinfunction "1_1") (pintype "passive"))
      (node (ref "U2") (pin "7") (pinfunction "PTE6_7") (pintype "bidirectional"))
    )
    (net (code "7") (name "MUX000") (class "Default")
      (node (ref "MUX0") (pin "4") (pinfunction "I/O0.0_4") (pintype "bidirectional"))
      (node (ref "T2") (pin "B") (pinfunction "B_B") (pintype "passive"))
    )
    (net (code "8") (name "MUX001") (class "Default")
      (node (ref "MUX0") (pin "5") (pinfunction "I/O0.1_5") (pintype "bidirectional"))
      (node (ref "T3") (pin "B") (pinfunction "B_B") (pintype "passive"))
    )
    (net (code "9") (name "MUX002") (class "Default")
      (node (ref "MUX0") (pin "6") (pinfunction "I/O0.2_6") (pintype "bidirectional"))
      (node (ref "T4") (pin "B") (pinfunction "B_B") (pintype "passive"))
    )
    (net (code "10") (name "MUX003") (class "Default")
      (node (ref "MUX0") (pin "7") (pinfunction "I/O0.3_7") (pintype "bidirectional"))
      (node (ref "T5") (pin "B") (pinfunction "B_B") (pintype "passive"))
    )
    (net (code "11") (name "MUX004") (class "Default")
      (node (ref "MUX0") (pin "8") (pinfunction "I/O0.4_8") (pintype "bidirectional"))
      (node (ref "T6") (pin "B") (pinfunction "B_B") (pintype "passive"))
    )
    (net (code "12") (name "MUX005") (class "Default")
      (node (ref "MUX0") (pin "9") (pinfunction "I/O0.5_9") (pintype "bidirectional"))
      (node (ref "T7") (pin "B") (pinfunction "B_B") (pintype "passive"))
    )
    (net (code "13") (name "MUX006") (class "Default")
      (node (ref "MUX0") (pin "10") (pinfunction "I/O0.6_10") (pintype "bidirectional"))
      (node (ref "T8") (pin "B") (pinfunction "B_B") (pintype "passive"))
    )
    (net (code "14") (name "MUX007") (class "Default")
      (node (ref "MUX0") (pin "11") (pinfunction "I/O0.7_11") (pintype "bidirectional"))
      (node (ref "T9") (pin "B") (pinfunction "B_B") (pintype "passive"))
    )
    (net (code "15") (name "MUX010") (class "Default")
      (node (ref "MUX0") (pin "13") (pinfunction "I/O1.0_13") (pintype "bidirectional"))
      (node (ref "T10") (pin "B") (pinfunction "B_B") (pintype "passive"))
    )
    (net (code "16") (name "MUX011") (class "Default")
      (node (ref "MUX0") (pin "14") (pinfunction "I/O1.1_14") (pintype "bidirectional"))
      (node (ref "T11") (pin "B") (pinfunction "B_B") (pintype "passive"))
    )
    (net (code "17") (name "MUX012") (class "Default")
      (node (ref "MUX0") (pin "15") (pinfunction "I/O1.2_15") (pintype "bidirectional"))
      (node (ref "T12") (pin "B") (pinfunction "B_B") (pintype "passive"))
    )
    (net (code "18") (name "MUX013") (class "Default")
      (node (ref "MUX0") (pin "16") (pinfunction "I/O1.3_16") (pintype "bidirectional"))
      (node (ref "T13") (pin "B") (pinfunction "B_B") (pintype "passive"))
    )
    (net (code "19") (name "MUX014") (class "Default")
      (node (ref "MUX0") (pin "17") (pinfunction "I/O1.4_17") (pintype "bidirectional"))
      (node (ref "T14") (pin "B") (pinfunction "B_B") (pintype "passive"))
    )
    (net (code "20") (name "MUX015") (class "Default")
      (node (ref "MUX0") (pin "18") (pinfunction "I/O1.5_18") (pintype "bidirectional"))
      (node (ref "T15") (pin "B") (pinfunction "B_B") (pintype "passive"))
    )
    (net (code "21") (name "MUX016") (class "Default")
      (node (ref "MUX0") (pin "19") (pinfunction "I/O1.6_19") (pintype "bidirectional"))
      (node (ref "T16") (pin "B") (pinfunction "B_B") (pintype "passive"))
    )
    (net (code "22") (name "MUX017") (class "Default")
      (node (ref "MUX0") (pin "20") (pinfunction "I/O1.7_20") (pintype "bidirectional"))
      (node (ref "T17") (pin "B") (pinfunction "B_B") (pintype "passive"))
    )
    (net (code "23") (name "MUX100") (class "Default")
      (node (ref "MUX1") (pin "4") (pinfunction "I/O0.0_4") (pintype "bidirectional"))
      (node (ref "T18") (pin "B") (pinfunction "B_B") (pintype "passive"))
    )
    (net (code "24") (name "MUX101") (class "Default")
      (node (ref "MUX1") (pin "5") (pinfunction "I/O0.1_5") (pintype "bidirectional"))
      (node (ref "T19") (pin "B") (pinfunction "B_B") (pintype "passive"))
    )
    (net (code "25") (name "MUX102") (class "Default")
      (node (ref "MUX1") (pin "6") (pinfunction "I/O0.2_6") (pintype "bidirectional"))
      (node (ref "T20") (pin "B") (pinfunction "B_B") (pintype "passive"))
    )
    (net (code "26") (name "MUX103") (class "Default")
      (node (ref "MUX1") (pin "7") (pinfunction "I/O0.3_7") (pintype "bidirectional"))
      (node (ref "T21") (pin "B") (pinfunction "B_B") (pintype "passive"))
    )
    (net (code "27") (name "MUX104") (class "Default")
      (node (ref "MUX1") (pin "8") (pinfunction "I/O0.4_8") (pintype "bidirectional"))
      (node (ref "T22") (pin "B") (pinfunction "B_B") (pintype "passive"))
    )
    (net (code "28") (name "MUX105") (class "Default")
      (node (ref "MUX1") (pin "9") (pinfunction "I/O0.5_9") (pintype "bidirectional"))
      (node (ref "T23") (pin "B") (pinfunction "B_B") (pintype "passive"))
    )
    (net (code "29") (name "MUX106") (class "Default")
      (node (ref "MUX1") (pin "10") (pinfunction "I/O0.6_10") (pintype "bidirectional"))
      (node (ref "T24") (pin "B") (pinfunction "B_B") (pintype "passive"))
    )
    (net (code "30") (name "MUX107") (class "Default")
      (node (ref "MUX1") (pin "11") (pinfunction "I/O0.7_11") (pintype "bidirectional"))
      (node (ref "T25") (pin "B") (pinfunction "B_B") (pintype "passive"))
    )
    (net (code "31") (name "MUX110") (class "Default")
      (node (ref "MUX1") (pin "13") (pinfunction "I/O1.0_13") (pintype "bidirectional"))
      (node (ref "T26") (pin "B") (pinfunction "B_B") (pintype "passive"))
    )
    (net (code "32") (name "MUX111") (class "Default")
      (node (ref "MUX1") (pin "14") (pinfunction "I/O1.1_14") (pintype "bidirectional"))
      (node (ref "T27") (pin "B") (pinfunction "B_B") (pintype "passive"))
    )
    (net (code "33") (name "MUX112") (class "Default")
      (node (ref "MUX1") (pin "15") (pinfunction "I/O1.2_15") (pintype "bidirectional"))
      (node (ref "T28") (pin "B") (pinfunction "B_B") (pintype "passive"))
    )
    (net (code "34") (name "MUX113") (class "Default")
      (node (ref "MUX1") (pin "16") (pinfunction "I/O1.3_16") (pintype "bidirectional"))
      (node (ref "T29") (pin "B") (pinfunction "B_B") (pintype "passive"))
    )
    (net (code "35") (name "MUX114") (class "Default")
      (node (ref "MUX1") (pin "17") (pinfunction "I/O1.4_17") (pintype "bidirectional"))
      (node (ref "T30") (pin "B") (pinfunction "B_B") (pintype "passive"))
    )
    (net (code "36") (name "MUX115") (class "Default")
      (node (ref "MUX1") (pin "18") (pinfunction "I/O1.5_18") (pintype "bidirectional"))
      (node (ref "T31") (pin "B") (pinfunction "B_B") (pintype "passive"))
    )
    (net (code "37") (name "MUX116") (class "Default")
      (node (ref "MUX1") (pin "19") (pinfunction "I/O1.6_19") (pintype "bidirectional"))
      (node (ref "T32") (pin "B") (pinfunction "B_B") (pintype "passive"))
    )
    (net (code "38") (name "MUX117") (class "Default")
      (node (ref "MUX1") (pin "20") (pinfunction "I/O1.7_20") (pintype "bidirectional"))
      (node (ref "T33") (pin "B") (pinfunction "B_B") (pintype "passive"))
    )
    (net (code "39") (name "MUX200") (class "Default")
      (node (ref "MUX2") (pin "4") (pinfunction "I/O0.0_4") (pintype "bidirectional"))
      (node (ref "T34") (pin "B") (pinfunction "B_B") (pintype "passive"))
    )
    (net (code "40") (name "MUX201") (class "Default")
      (node (ref "MUX2") (pin "5") (pinfunction "I/O0.1_5") (pintype "bidirectional"))
      (node (ref "T35") (pin "B") (pinfunction "B_B") (pintype "passive"))
    )
    (net (code "41") (name "MUX202") (class "Default")
      (node (ref "MUX2") (pin "6") (pinfunction "I/O0.2_6") (pintype "bidirectional"))
      (node (ref "T36") (pin "B") (pinfunction "B_B") (pintype "passive"))
    )
    (net (code "42") (name "MUX203") (class "Default")
      (node (ref "MUX2") (pin "7") (pinfunction "I/O0.3_7") (pintype "bidirectional"))
      (node (ref "T37") (pin "B") (pinfunction "B_B") (pintype "passive"))
    )
    (net (code "43") (name "MUX204") (class "Default")
      (node (ref "MUX2") (pin "8") (pinfunction "I/O0.4_8") (pintype "bidirectional"))
      (node (ref "T38") (pin "B") (pinfunction "B_B") (pintype "passive"))
    )
    (net (code "44") (name "MUX205") (class "Default")
      (node (ref "MUX2") (pin "9") (pinfunction "I/O0.5_9") (pintype "bidirectional"))
      (node (ref "T39") (pin "B") (pinfunction "B_B") (pintype "passive"))
    )
    (net (code "45") (name "MUX206") (class "Default")
      (node (ref "MUX2") (pin "10") (pinfunction "I/O0.6_10") (pintype "bidirectional"))
      (node (ref "T40") (pin "B") (pinfunction "B_B") (pintype "passive"))
    )
    (net (code "46") (name "MUX207") (class "Default")
      (node (ref "MUX2") (pin "11") (pinfunction "I/O0.7_11") (pintype "bidirectional"))
      (node (ref "T41") (pin "B") (pinfunction "B_B") (pintype "passive"))
    )
    (net (code "47") (name "MUX210") (class "Default")
      (node (ref "MUX2") (pin "13") (pinfunction "I/O1.0_13") (pintype "bidirectional"))
      (node (ref "T42") (pin "B") (pinfunction "B_B") (pintype "passive"))
    )
    (net (code "48") (name "MUX211") (class "Default")
      (node (ref "MUX2") (pin "14") (pinfunction "I/O1.1_14") (pintype "bidirectional"))
      (node (ref "T43") (pin "B") (pinfunction "B_B") (pintype "passive"))
    )
    (net (code "49") (name "MUX212") (class "Default")
      (node (ref "MUX2") (pin "15") (pinfunction "I/O1.2_15") (pintype "bidirectional"))
      (node (ref "T44") (pin "B") (pinfunction "B_B") (pintype "passive"))
    )
    (net (code "50") (name "MUX213") (class "Default")
      (node (ref "MUX2") (pin "16") (pinfunction "I/O1.3_16") (pintype "bidirectional"))
      (node (ref "T45") (pin "B") (pinfunction "B_B") (pintype "passive"))
    )
    (net (code "51") (name "MUX214") (class "Default")
      (node (ref "MUX2") (pin "17") (pinfunction "I/O1.4_17") (pintype "bidirectional"))
      (node (ref "T46") (pin "B") (pinfunction "B_B") (pintype "passive"))
    )
    (net (code "52") (name "MUX215") (class "Default")
      (node (ref "MUX2") (pin "18") (pinfunction "I/O1.5_18") (pintype "bidirectional"))
      (node (ref "T47") (pin "B") (pinfunction "B_B") (pintype "passive"))
    )
    (net (code "53") (name "MUX216") (class "Default")
      (node (ref "MUX2") (pin "19") (pinfunction "I/O1.6_19") (pintype "bidirectional"))
      (node (ref "T48") (pin "B") (pinfunction "B_B") (pintype "passive"))
    )
    (net (code "54") (name "MUX217") (class "Default")
      (node (ref "MUX2") (pin "20") (pinfunction "I/O1.7_20") (pintype "bidirectional"))
      (node (ref "T49") (pin "B") (pinfunction "B_B") (pintype "passive"))
    )
    (net (code "55") (name "MUX300") (class "Default")
      (node (ref "MUX3") (pin "4") (pinfunction "I/O0.0_4") (pintype "bidirectional"))
      (node (ref "T50") (pin "B") (pinfunction "B_B") (pintype "passive"))
    )
    (net (code "56") (name "MUX301") (class "Default")
      (node (ref "MUX3") (pin "5") (pinfunction "I/O0.1_5") (pintype "bidirectional"))
      (node (ref "T51") (pin "B") (pinfunction "B_B") (pintype "passive"))
    )
    (net (code "57") (name "MUX302") (class "Default")
      (node (ref "MUX3") (pin "6") (pinfunction "I/O0.2_6") (pintype "bidirectional"))
      (node (ref "T52") (pin "B") (pinfunction "B_B") (pintype "passive"))
    )
    (net (code "58") (name "MUX303") (class "Default")
      (node (ref "MUX3") (pin "7") (pinfunction "I/O0.3_7") (pintype "bidirectional"))
      (node (ref "T53") (pin "B") (pinfunction "B_B") (pintype "passive"))
    )
    (net (code "59") (name "MUX304") (class "Default")
      (node (ref "MUX3") (pin "8") (pinfunction "I/O0.4_8") (pintype "bidirectional"))
      (node (ref "T54") (pin "B") (pinfunction "B_B") (pintype "passive"))
    )
    (net (code "60") (name "MUX305") (class "Default")
      (node (ref "MUX3") (pin "9") (pinfunction "I/O0.5_9") (pintype "bidirectional"))
      (node (ref "T55") (pin "B") (pinfunction "B_B") (pintype "passive"))
    )
    (net (code "61") (name "MUX306") (class "Default")
      (node (ref "MUX3") (pin "10") (pinfunction "I/O0.6_10") (pintype "bidirectional"))
      (node (ref "T56") (pin "B") (pinfunction "B_B") (pintype "passive"))
    )
    (net (code "62") (name "MUX307") (class "Default")
      (node (ref "MUX3") (pin "11") (pinfunction "I/O0.7_11") (pintype "bidirectional"))
      (node (ref "T57") (pin "B") (pinfunction "B_B") (pintype "passive"))
    )
    (net (code "63") (name "MUX310") (class "Default")
      (node (ref "MUX3") (pin "13") (pinfunction "I/O1.0_13") (pintype "bidirectional"))
      (node (ref "T58") (pin "B") (pinfunction "B_B") (pintype "passive"))
    )
    (net (code "64") (name "MUX311") (class "Default")
      (node (ref "MUX3") (pin "14") (pinfunction "I/O1.1_14") (pintype "bidirectional"))
      (node (ref "T59") (pin "B") (pinfunction "B_B") (pintype "passive"))
    )
    (net (code "65") (name "MUX312") (class "Default")
      (node (ref "MUX3") (pin "15") (pinfunction "I/O1.2_15") (pintype "bidirectional"))
      (node (ref "T60") (pin "B") (pinfunction "B_B") (pintype "passive"))
    )
    (net (code "66") (name "MUX313") (class "Default")
      (node (ref "MUX3") (pin "16") (pinfunction "I/O1.3_16") (pintype "bidirectional"))
      (node (ref "T61") (pin "B") (pinfunction "B_B") (pintype "passive"))
    )
    (net (code "67") (name "MUX314") (class "Default")
      (node (ref "MUX3") (pin "17") (pinfunction "I/O1.4_17") (pintype "bidirectional"))
    )
    (net (code "68") (name "MUX315") (class "Default")
      (node (ref "MUX3") (pin "18") (pinfunction "I/O1.5_18") (pintype "bidirectional"))
    )
    (net (code "69") (name "MUX316") (class "Default")
      (node (ref "MUX3") (pin "19") (pinfunction "I/O1.6_19") (pintype "bidirectional"))
    )
    (net (code "70") (name "MUX317") (class "Default")
      (node (ref "MUX3") (pin "20") (pinfunction "I/O1.7_20") (pintype "bidirectional"))
    )
    (net (code "71") (name "NIXIE_PWR") (class "Default")
      (node (ref "Q1") (pin "3") (pinfunction "C_3") (pintype "passive"))
      (node (ref "R1") (pin "2") (pinfunction "2_2") (pintype "passive"))
      (node (ref "R2") (pin "2") (pinfunction "2_2") (pintype "passive"))
      (node (ref "R3") (pin "2") (pinfunction "2_2") (pintype "passive"))
      (node (ref "R4") (pin "2") (pinfunction "2_2") (pintype "passive"))
      (node (ref "R5") (pin "2") (pinfunction "2_2") (pintype "passive"))
      (node (ref "R6") (pin "2") (pinfunction "2_2") (pintype "passive"))
    )
    (net (code "72") (name "NIXIE_PWR_PWM") (class "Default")
      (node (ref "R25") (pin "1") (pinfunction "1_1") (pintype "passive"))
      (node (ref "U2") (pin "6") (pinfunction "PTE5_6") (pintype "bidirectional"))
    )
    (net (code "73") (name "Net-(D2-A)") (class "Default")
      (node (ref "D2") (pin "4") (pinfunction "A_4") (pintype "bidirectional"))
      (node (ref "R26") (pin "1") (pinfunction "1_1") (pintype "passive"))
    )
    (net (code "74") (name "Net-(D2-BLU)") (class "Default")
      (node (ref "D2") (pin "3") (pinfunction "BLU_3") (pintype "bidirectional"))
      (node (ref "R30") (pin "2") (pinfunction "2_2") (pintype "passive"))
    )
    (net (code "75") (name "Net-(D2-GRN)") (class "Default")
      (node (ref "D2") (pin "2") (pinfunction "GRN_2") (pintype "bidirectional"))
      (node (ref "R31") (pin "2") (pinfunction "2_2") (pintype "passive"))
    )
    (net (code "76") (name "Net-(D2-RED)") (class "Default")
      (node (ref "D2") (pin "1") (pinfunction "RED_1") (pintype "bidirectional"))
      (node (ref "R29") (pin "2") (pinfunction "2_2") (pintype "passive"))
    )
    (net (code "77") (name "Net-(D3-A)") (class "Default")
      (node (ref "D3") (pin "4") (pinfunction "A_4") (pintype "bidirectional"))
      (node (ref "R33") (pin "1") (pinfunction "1_1") (pintype "passive"))
    )
    (net (code "78") (name "Net-(D3-BLU)") (class "Default")
      (node (ref "D3") (pin "3") (pinfunction "BLU_3") (pintype "bidirectional"))
      (node (ref "R28") (pin "2") (pinfunction "2_2") (pintype "passive"))
    )
    (net (code "79") (name "Net-(D3-GRN)") (class "Default")
      (node (ref "D3") (pin "2") (pinfunction "GRN_2") (pintype "bidirectional"))
      (node (ref "R32") (pin "2") (pinfunction "2_2") (pintype "passive"))
    )
    (net (code "80") (name "Net-(D3-RED)") (class "Default")
      (node (ref "D3") (pin "1") (pinfunction "RED_1") (pintype "bidirectional"))
      (node (ref "R27") (pin "2") (pinfunction "2_2") (pintype "passive"))
    )
    (net (code "81") (name "Net-(D4-A)") (class "Default")
      (node (ref "D4") (pin "4") (pinfunction "A_4") (pintype "bidirectional"))
      (node (ref "R37") (pin "1") (pinfunction "1_1") (pintype "passive"))
    )
    (net (code "82") (name "Net-(D4-BLU)") (class "Default")
      (node (ref "D4") (pin "3") (pinfunction "BLU_3") (pintype "bidirectional"))
      (node (ref "R35") (pin "2") (pinfunction "2_2") (pintype "passive"))
    )
    (net (code "83") (name "Net-(D4-GRN)") (class "Default")
      (node (ref "D4") (pin "2") (pinfunction "GRN_2") (pintype "bidirectional"))
      (node (ref "R36") (pin "2") (pinfunction "2_2") (pintype "passive"))
    )
    (net (code "84") (name "Net-(D4-RED)") (class "Default")
      (node (ref "D4") (pin "1") (pinfunction "RED_1") (pintype "bidirectional"))
      (node (ref "R34") (pin "2") (pinfunction "2_2") (pintype "passive"))
    )
    (net (code "85") (name "Net-(D5-A)") (class "Default")
      (node (ref "D5") (pin "4") (pinfunction "A_4") (pintype "bidirectional"))
      (node (ref "R41") (pin "1") (pinfunction "1_1") (pintype "passive"))
    )
    (net (code "86") (name "Net-(D5-BLU)") (class "Default")
      (node (ref "D5") (pin "3") (pinfunction "BLU_3") (pintype "bidirectional"))
      (node (ref "R39") (pin "2") (pinfunction "2_2") (pintype "passive"))
    )
    (net (code "87") (name "Net-(D5-GRN)") (class "Default")
      (node (ref "D5") (pin "2") (pinfunction "GRN_2") (pintype "bidirectional"))
      (node (ref "R40") (pin "2") (pinfunction "2_2") (pintype "passive"))
    )
    (net (code "88") (name "Net-(D5-RED)") (class "Default")
      (node (ref "D5") (pin "1") (pinfunction "RED_1") (pintype "bidirectional"))
      (node (ref "R38") (pin "2") (pinfunction "2_2") (pintype "passive"))
    )
    (net (code "89") (name "Net-(D6-A)") (class "Default")
      (node (ref "D6") (pin "4") (pinfunction "A_4") (pintype "bidirectional"))
      (node (ref "R45") (pin "1") (pinfunction "1_1") (pintype "passive"))
    )
    (net (code "90") (name "Net-(D6-BLU)") (class "Default")
      (node (ref "D6") (pin "3") (pinfunction "BLU_3") (pintype "bidirectional"))
      (node (ref "R43") (pin "2") (pinfunction "2_2") (pintype "passive"))
    )
    (net (code "91") (name "Net-(D6-GRN)") (class "Default")
      (node (ref "D6") (pin "2") (pinfunction "GRN_2") (pintype "bidirectional"))
      (node (ref "R44") (pin "2") (pinfunction "2_2") (pintype "passive"))
    )
    (net (code "92") (name "Net-(D6-RED)") (class "Default")
      (node (ref "D6") (pin "1") (pinfunction "RED_1") (pintype "bidirectional"))
      (node (ref "R42") (pin "2") (pinfunction "2_2") (pintype "passive"))
    )
    (net (code "93") (name "Net-(D7-A)") (class "Default")
      (node (ref "D7") (pin "4") (pinfunction "A_4") (pintype "bidirectional"))
      (node (ref "R49") (pin "1") (pinfunction "1_1") (pintype "passive"))
    )
    (net (code "94") (name "Net-(D7-BLU)") (class "Default")
      (node (ref "D7") (pin "3") (pinfunction "BLU_3") (pintype "bidirectional"))
      (node (ref "R47") (pin "2") (pinfunction "2_2") (pintype "passive"))
    )
    (net (code "95") (name "Net-(D7-GRN)") (class "Default")
      (node (ref "D7") (pin "2") (pinfunction "GRN_2") (pintype "bidirectional"))
      (node (ref "R48") (pin "2") (pinfunction "2_2") (pintype "passive"))
    )
    (net (code "96") (name "Net-(D7-RED)") (class "Default")
      (node (ref "D7") (pin "1") (pinfunction "RED_1") (pintype "bidirectional"))
      (node (ref "R46") (pin "2") (pinfunction "2_2") (pintype "passive"))
    )
    (net (code "97") (name "Net-(N1-Pad0)") (class "Default")
      (node (ref "N1") (pin "0") (pinfunction "0_0") (pintype "bidirectional"))
      (node (ref "T2") (pin "C") (pinfunction "C_C") (pintype "passive"))
    )
    (net (code "98") (name "Net-(N1-Pad1)") (class "Default")
      (node (ref "N1") (pin "1") (pinfunction "1_1") (pintype "bidirectional"))
      (node (ref "T3") (pin "C") (pinfunction "C_C") (pintype "passive"))
    )
    (net (code "99") (name "Net-(N1-Pad2)") (class "Default")
      (node (ref "N1") (pin "2") (pinfunction "2_2") (pintype "bidirectional"))
      (node (ref "T4") (pin "C") (pinfunction "C_C") (pintype "passive"))
    )
    (net (code "100") (name "Net-(N1-Pad3)") (class "Default")
      (node (ref "N1") (pin "3") (pinfunction "3_3") (pintype "bidirectional"))
      (node (ref "T5") (pin "C") (pinfunction "C_C") (pintype "passive"))
    )
    (net (code "101") (name "Net-(N1-Pad4)") (class "Default")
      (node (ref "N1") (pin "4") (pinfunction "4_4") (pintype "bidirectional"))
      (node (ref "T6") (pin "C") (pinfunction "C_C") (pintype "passive"))
    )
    (net (code "102") (name "Net-(N1-Pad5)") (class "Default")
      (node (ref "N1") (pin "5") (pinfunction "5_5") (pintype "bidirectional"))
      (node (ref "T7") (pin "C") (pinfunction "C_C") (pintype "passive"))
    )
    (net (code "103") (name "Net-(N1-Pad6)") (class "Default")
      (node (ref "N1") (pin "6") (pinfunction "6_6") (pintype "bidirectional"))
      (node (ref "T8") (pin "C") (pinfunction "C_C") (pintype "passive"))
    )
    (net (code "104") (name "Net-(N1-Pad7)") (class "Default")
      (node (ref "N1") (pin "7") (pinfunction "7_7") (pintype "bidirectional"))
      (node (ref "T9") (pin "C") (pinfunction "C_C") (pintype "passive"))
    )
    (net (code "105") (name "Net-(N1-Pad8)") (class "Default")
      (node (ref "N1") (pin "8") (pinfunction "8_8") (pintype "bidirectional"))
      (node (ref "T10") (pin "C") (pinfunction "C_C") (pintype "passive"))
    )
    (net (code "106") (name "Net-(N1-Pad9)") (class "Default")
      (node (ref "N1") (pin "9") (pinfunction "9_9") (pintype "bidirectional"))
      (node (ref "T11") (pin "C") (pinfunction "C_C") (pintype "passive"))
    )
    (net (code "107") (name "Net-(N1-PadA)") (class "Default")
      (node (ref "N1") (pin "A") (pinfunction "A_A") (pintype "bidirectional"))
      (node (ref "N1") (pin "A2") (pinfunction "A2_A2") (pintype "bidirectional"))
      (node (ref "R3") (pin "1") (pinfunction "1_1") (pintype "passive"))
    )
    (net (code "108") (name "Net-(N2-Pad0)") (class "Default")
      (node (ref "N2") (pin "0") (pinfunction "0_0") (pintype "bidirectional"))
      (node (ref "T12") (pin "C") (pinfunction "C_C") (pintype "passive"))
    )
    (net (code "109") (name "Net-(N2-Pad1)") (class "Default")
      (node (ref "N2") (pin "1") (pinfunction "1_1") (pintype "bidirectional"))
      (node (ref "T13") (pin "C") (pinfunction "C_C") (pintype "passive"))
    )
    (net (code "110") (name "Net-(N2-Pad2)") (class "Default")
      (node (ref "N2") (pin "2") (pinfunction "2_2") (pintype "bidirectional"))
      (node (ref "T14") (pin "C") (pinfunction "C_C") (pintype "passive"))
    )
    (net (code "111") (name "Net-(N2-Pad3)") (class "Default")
      (node (ref "N2") (pin "3") (pinfunction "3_3") (pintype "bidirectional"))
      (node (ref "T15") (pin "C") (pinfunction "C_C") (pintype "passive"))
    )
    (net (code "112") (name "Net-(N2-Pad4)") (class "Default")
      (node (ref "N2") (pin "4") (pinfunction "4_4") (pintype "bidirectional"))
      (node (ref "T16") (pin "C") (pinfunction "C_C") (pintype "passive"))
    )
    (net (code "113") (name "Net-(N2-Pad5)") (class "Default")
      (node (ref "N2") (pin "5") (pinfunction "5_5") (pintype "bidirectional"))
      (node (ref "T17") (pin "C") (pinfunction "C_C") (pintype "passive"))
    )
    (net (code "114") (name "Net-(N2-Pad6)") (class "Default")
      (node (ref "N2") (pin "6") (pinfunction "6_6") (pintype "bidirectional"))
      (node (ref "T18") (pin "C") (pinfunction "C_C") (pintype "passive"))
    )
    (net (code "115") (name "Net-(N2-Pad7)") (class "Default")
      (node (ref "N2") (pin "7") (pinfunction "7_7") (pintype "bidirectional"))
      (node (ref "T19") (pin "C") (pinfunction "C_C") (pintype "passive"))
    )
    (net (code "116") (name "Net-(N2-Pad8)") (class "Default")
      (node (ref "N2") (pin "8") (pinfunction "8_8") (pintype "bidirectional"))
      (node (ref "T20") (pin "C") (pinfunction "C_C") (pintype "passive"))
    )
    (net (code "117") (name "Net-(N2-Pad9)") (class "Default")
      (node (ref "N2") (pin "9") (pinfunction "9_9") (pintype "bidirectional"))
      (node (ref "T21") (pin "C") (pinfunction "C_C") (pintype "passive"))
    )
    (net (code "118") (name "Net-(N2-PadA)") (class "Default")
      (node (ref "N2") (pin "A") (pinfunction "A_A") (pintype "bidirectional"))
      (node (ref "N2") (pin "A2") (pinfunction "A2_A2") (pintype "bidirectional"))
      (node (ref "R1") (pin "1") (pinfunction "1_1") (pintype "passive"))
    )
    (net (code "119") (name "Net-(N3-Pad0)") (class "Default")
      (node (ref "N3") (pin "0") (pinfunction "0_0") (pintype "bidirectional"))
      (node (ref "T22") (pin "C") (pinfunction "C_C") (pintype "passive"))
    )
    (net (code "120") (name "Net-(N3-Pad1)") (class "Default")
      (node (ref "N3") (pin "1") (pinfunction "1_1") (pintype "bidirectional"))
      (node (ref "T23") (pin "C") (pinfunction "C_C") (pintype "passive"))
    )
    (net (code "121") (name "Net-(N3-Pad2)") (class "Default")
      (node (ref "N3") (pin "2") (pinfunction "2_2") (pintype "bidirectional"))
      (node (ref "T24") (pin "C") (pinfunction "C_C") (pintype "passive"))
    )
    (net (code "122") (name "Net-(N3-Pad3)") (class "Default")
      (node (ref "N3") (pin "3") (pinfunction "3_3") (pintype "bidirectional"))
      (node (ref "T25") (pin "C") (pinfunction "C_C") (pintype "passive"))
    )
    (net (code "123") (name "Net-(N3-Pad4)") (class "Default")
      (node (ref "N3") (pin "4") (pinfunction "4_4") (pintype "bidirectional"))
      (node (ref "T26") (pin "C") (pinfunction "C_C") (pintype "passive"))
    )
    (net (code "124") (name "Net-(N3-Pad5)") (class "Default")
      (node (ref "N3") (pin "5") (pinfunction "5_5") (pintype "bidirectional"))
      (node (ref "T27") (pin "C") (pinfunction "C_C") (pintype "passive"))
    )
    (net (code "125") (name "Net-(N3-Pad6)") (class "Default")
      (node (ref "N3") (pin "6") (pinfunction "6_6") (pintype "bidirectional"))
      (node (ref "T28") (pin "C") (pinfunction "C_C") (pintype "passive"))
    )
    (net (code "126") (name "Net-(N3-Pad7)") (class "Default")
      (node (ref "N3") (pin "7") (pinfunction "7_7") (pintype "bidirectional"))
      (node (ref "T29") (pin "C") (pinfunction "C_C") (pintype "passive"))
    )
    (net (code "127") (name "Net-(N3-Pad8)") (class "Default")
      (node (ref "N3") (pin "8") (pinfunction "8_8") (pintype "bidirectional"))
      (node (ref "T30") (pin "C") (pinfunction "C_C") (pintype "passive"))
    )
    (net (code "128") (name "Net-(N3-Pad9)") (class "Default")
      (node (ref "N3") (pin "9") (pinfunction "9_9") (pintype "bidirectional"))
      (node (ref "T31") (pin "C") (pinfunction "C_C") (pintype "passive"))
    )
    (net (code "129") (name "Net-(N3-PadA)") (class "Default")
      (node (ref "N3") (pin "A") (pinfunction "A_A") (pintype "bidirectional"))
      (node (ref "N3") (pin "A2") (pinfunction "A2_A2") (pintype "bidirectional"))
      (node (ref "R2") (pin "1") (pinfunction "1_1") (pintype "passive"))
    )
    (net (code "130") (name "Net-(N4-Pad0)") (class "Default")
      (node (ref "N4") (pin "0") (pinfunction "0_0") (pintype "bidirectional"))
      (node (ref "T32") (pin "C") (pinfunction "C_C") (pintype "passive"))
    )
    (net (code "131") (name "Net-(N4-Pad1)") (class "Default")
      (node (ref "N4") (pin "1") (pinfunction "1_1") (pintype "bidirectional"))
      (node (ref "T33") (pin "C") (pinfunction "C_C") (pintype "passive"))
    )
    (net (code "132") (name "Net-(N4-Pad2)") (class "Default")
      (node (ref "N4") (pin "2") (pinfunction "2_2") (pintype "bidirectional"))
      (node (ref "T34") (pin "C") (pinfunction "C_C") (pintype "passive"))
    )
    (net (code "133") (name "Net-(N4-Pad3)") (class "Default")
      (node (ref "N4") (pin "3") (pinfunction "3_3") (pintype "bidirectional"))
      (node (ref "T35") (pin "C") (pinfunction "C_C") (pintype "passive"))
    )
    (net (code "134") (name "Net-(N4-Pad4)") (class "Default")
      (node (ref "N4") (pin "4") (pinfunction "4_4") (pintype "bidirectional"))
      (node (ref "T36") (pin "C") (pinfunction "C_C") (pintype "passive"))
    )
    (net (code "135") (name "Net-(N4-Pad5)") (class "Default")
      (node (ref "N4") (pin "5") (pinfunction "5_5") (pintype "bidirectional"))
      (node (ref "T37") (pin "C") (pinfunction "C_C") (pintype "passive"))
    )
    (net (code "136") (name "Net-(N4-Pad6)") (class "Default")
      (node (ref "N4") (pin "6") (pinfunction "6_6") (pintype "bidirectional"))
      (node (ref "T38") (pin "C") (pinfunction "C_C") (pintype "passive"))
    )
    (net (code "137") (name "Net-(N4-Pad7)") (class "Default")
      (node (ref "N4") (pin "7") (pinfunction "7_7") (pintype "bidirectional"))
      (node (ref "T39") (pin "C") (pinfunction "C_C") (pintype "passive"))
    )
    (net (code "138") (name "Net-(N4-Pad8)") (class "Default")
      (node (ref "N4") (pin "8") (pinfunction "8_8") (pintype "bidirectional"))
      (node (ref "T40") (pin "C") (pinfunction "C_C") (pintype "passive"))
    )
    (net (code "139") (name "Net-(N4-Pad9)") (class "Default")
      (node (ref "N4") (pin "9") (pinfunction "9_9") (pintype "bidirectional"))
      (node (ref "T41") (pin "C") (pinfunction "C_C") (pintype "passive"))
    )
    (net (code "140") (name "Net-(N4-PadA)") (class "Default")
      (node (ref "N4") (pin "A") (pinfunction "A_A") (pintype "bidirectional"))
      (node (ref "N4") (pin "A2") (pinfunction "A2_A2") (pintype "bidirectional"))
      (node (ref "R4") (pin "1") (pinfunction "1_1") (pintype "passive"))
    )
    (net (code "141") (name "Net-(N5-Pad0)") (class "Default")
      (node (ref "N5") (pin "0") (pinfunction "0_0") (pintype "bidirectional"))
      (node (ref "T42") (pin "C") (pinfunction "C_C") (pintype "passive"))
    )
    (net (code "142") (name "Net-(N5-Pad1)") (class "Default")
      (node (ref "N5") (pin "1") (pinfunction "1_1") (pintype "bidirectional"))
      (node (ref "T43") (pin "C") (pinfunction "C_C") (pintype "passive"))
    )
    (net (code "143") (name "Net-(N5-Pad2)") (class "Default")
      (node (ref "N5") (pin "2") (pinfunction "2_2") (pintype "bidirectional"))
      (node (ref "T44") (pin "C") (pinfunction "C_C") (pintype "passive"))
    )
    (net (code "144") (name "Net-(N5-Pad3)") (class "Default")
      (node (ref "N5") (pin "3") (pinfunction "3_3") (pintype "bidirectional"))
      (node (ref "T45") (pin "C") (pinfunction "C_C") (pintype "passive"))
    )
    (net (code "145") (name "Net-(N5-Pad4)") (class "Default")
      (node (ref "N5") (pin "4") (pinfunction "4_4") (pintype "bidirectional"))
      (node (ref "T46") (pin "C") (pinfunction "C_C") (pintype "passive"))
    )
    (net (code "146") (name "Net-(N5-Pad5)") (class "Default")
      (node (ref "N5") (pin "5") (pinfunction "5_5") (pintype "bidirectional"))
      (node (ref "T47") (pin "C") (pinfunction "C_C") (pintype "passive"))
    )
    (net (code "147") (name "Net-(N5-Pad6)") (class "Default")
      (node (ref "N5") (pin "6") (pinfunction "6_6") (pintype "bidirectional"))
      (node (ref "T48") (pin "C") (pinfunction "C_C") (pintype "passive"))
    )
    (net (code "148") (name "Net-(N5-Pad7)") (class "Default")
      (node (ref "N5") (pin "7") (pinfunction "7_7") (pintype "bidirectional"))
      (node (ref "T49") (pin "C") (pinfunction "C_C") (pintype "passive"))
    )
    (net (code "149") (name "Net-(N5-Pad8)") (class "Default")
      (node (ref "N5") (pin "8") (pinfunction "8_8") (pintype "bidirectional"))
      (node (ref "T50") (pin "C") (pinfunction "C_C") (pintype "passive"))
    )
    (net (code "150") (name "Net-(N5-Pad9)") (class "Default")
      (node (ref "N5") (pin "9") (pinfunction "9_9") (pintype "bidirectional"))
      (node (ref "T51") (pin "C") (pinfunction "C_C") (pintype "passive"))
    )
    (net (code "151") (name "Net-(N5-PadA)") (class "Default")
      (node (ref "N5") (pin "A") (pinfunction "A_A") (pintype "bidirectional"))
      (node (ref "N5") (pin "A2") (pinfunction "A2_A2") (pintype "bidirectional"))
      (node (ref "R5") (pin "1") (pinfunction "1_1") (pintype "passive"))
    )
    (net (code "152") (name "Net-(N6-Pad0)") (class "Default")
      (node (ref "N6") (pin "0") (pinfunction "0_0") (pintype "bidirectional"))
      (node (ref "T52") (pin "C") (pinfunction "C_C") (pintype "passive"))
    )
    (net (code "153") (name "Net-(N6-Pad1)") (class "Default")
      (node (ref "N6") (pin "1") (pinfunction "1_1") (pintype "bidirectional"))
      (node (ref "T53") (pin "C") (pinfunction "C_C") (pintype "passive"))
    )
    (net (code "154") (name "Net-(N6-Pad2)") (class "Default")
      (node (ref "N6") (pin "2") (pinfunction "2_2") (pintype "bidirectional"))
      (node (ref "T54") (pin "C") (pinfunction "C_C") (pintype "passive"))
    )
    (net (code "155") (name "Net-(N6-Pad3)") (class "Default")
      (node (ref "N6") (pin "3") (pinfunction "3_3") (pintype "bidirectional"))
      (node (ref "T55") (pin "C") (pinfunction "C_C") (pintype "passive"))
    )
    (net (code "156") (name "Net-(N6-Pad4)") (class "Default")
      (node (ref "N6") (pin "4") (pinfunction "4_4") (pintype "bidirectional"))
      (node (ref "T56") (pin "C") (pinfunction "C_C") (pintype "passive"))
    )
    (net (code "157") (name "Net-(N6-Pad5)") (class "Default")
      (node (ref "N6") (pin "5") (pinfunction "5_5") (pintype "bidirectional"))
      (node (ref "T57") (pin "C") (pinfunction "C_C") (pintype "passive"))
    )
    (net (code "158") (name "Net-(N6-Pad6)") (class "Default")
      (node (ref "N6") (pin "6") (pinfunction "6_6") (pintype "bidirectional"))
      (node (ref "T58") (pin "C") (pinfunction "C_C") (pintype "passive"))
    )
    (net (code "159") (name "Net-(N6-Pad7)") (class "Default")
      (node (ref "N6") (pin "7") (pinfunction "7_7") (pintype "bidirectional"))
      (node (ref "T59") (pin "C") (pinfunction "C_C") (pintype "passive"))
    )
    (net (code "160") (name "Net-(N6-Pad8)") (class "Default")
      (node (ref "N6") (pin "8") (pinfunction "8_8") (pintype "bidirectional"))
      (node (ref "T60") (pin "C") (pinfunction "C_C") (pintype "passive"))
    )
    (net (code "161") (name "Net-(N6-Pad9)") (class "Default")
      (node (ref "N6") (pin "9") (pinfunction "9_9") (pintype "bidirectional"))
      (node (ref "T61") (pin "C") (pinfunction "C_C") (pintype "passive"))
    )
    (net (code "162") (name "Net-(N6-PadA)") (class "Default")
      (node (ref "N6") (pin "A") (pinfunction "A_A") (pintype "bidirectional"))
      (node (ref "N6") (pin "A2") (pinfunction "A2_A2") (pintype "bidirectional"))
      (node (ref "R6") (pin "1") (pinfunction "1_1") (pintype "passive"))
    )
    (net (code "163") (name "Net-(Q1-B)") (class "Default")
      (node (ref "Q1") (pin "1") (pinfunction "B_1") (pintype "passive"))
      (node (ref "R23") (pin "1") (pinfunction "1_1") (pintype "passive"))
      (node (ref "R24") (pin "2") (pinfunction "2_2") (pintype "passive"))
    )
    (net (code "164") (name "Net-(R24-Pad1)") (class "Default")
      (node (ref "R24") (pin "1") (pinfunction "1_1") (pintype "passive"))
      (node (ref "T1") (pin "C") (pinfunction "C_C") (pintype "passive"))
    )
    (net (code "165") (name "Net-(R25-Pad2)") (class "Default")
      (node (ref "R25") (pin "2") (pinfunction "2_2") (pintype "passive"))
      (node (ref "T1") (pin "B") (pinfunction "B_B") (pintype "passive"))
    )
    (net (code "166") (name "PTA0") (class "Default")
      (node (ref "J2") (pin "9") (pinfunction "9_9") (pintype "passive"))
      (node (ref "U2") (pin "34") (pinfunction "PTA0_34") (pintype "bidirectional"))
    )
    (net (code "167") (name "PTA2") (class "Default")
      (node (ref "J2") (pin "8") (pinfunction "8_8") (pintype "passive"))
      (node (ref "U2") (pin "36") (pinfunction "PTA2_36") (pintype "bidirectional"))
    )
    (net (code "168") (name "PTA3") (class "Default")
      (node (ref "J2") (pin "10") (pinfunction "10_10") (pintype "passive"))
      (node (ref "U2") (pin "37") (pinfunction "PTA3_37") (pintype "bidirectional"))
    )
    (net (code "169") (name "RESET") (class "Default")
      (node (ref "J2") (pin "6") (pinfunction "6_6") (pintype "passive"))
      (node (ref "R15") (pin "1") (pinfunction "1_1") (pintype "passive"))
      (node (ref "U2") (pin "52") (pinfunction "RESET_B_52") (pintype "passive"))
    )
    (net (code "170") (name "SCL") (class "Default")
      (node (ref "MUX0") (pin "22") (pinfunction "SCL_22") (pintype "input"))
      (node (ref "MUX1") (pin "22") (pinfunction "SCL_22") (pintype "input"))
      (node (ref "MUX2") (pin "22") (pinfunction "SCL_22") (pintype "input"))
      (node (ref "MUX3") (pin "22") (pinfunction "SCL_22") (pintype "input"))
      (node (ref "R22") (pin "1") (pinfunction "1_1") (pintype "passive"))
      (node (ref "U2") (pin "55") (pinfunction "PTB2_55") (pintype "bidirectional"))
    )
    (net (code "171") (name "SDA") (class "Default")
      (node (ref "MUX0") (pin "23") (pinfunction "SDA_23") (pintype "bidirectional"))
      (node (ref "MUX1") (pin "23") (pinfunction "SDA_23") (pintype "bidirectional"))
      (node (ref "MUX2") (pin "23") (pinfunction "SDA_23") (pintype "bidirectional"))
      (node (ref "MUX3") (pin "23") (pinfunction "SDA_23") (pintype "bidirectional"))
      (node (ref "R21") (pin "1") (pinfunction "1_1") (pintype "passive"))
      (node (ref "U2") (pin "56") (pinfunction "PTB3_56") (pintype "bidirectional"))
    )
    (net (code "172") (name "SHDN") (class "Default")
      (node (ref "R16") (pin "1") (pinfunction "1_1") (pintype "passive"))
      (node (ref "U$1") (pin "SHDN") (pinfunction "SHDN_SHDN") (pintype "bidirectional"))
      (node (ref "U2") (pin "90") (pinfunction "PTC16_90") (pintype "bidirectional"))
    )
    (net (code "173") (name "V170") (class "Default")
      (node (ref "Q1") (pin "2") (pinfunction "E_2") (pintype "passive"))
      (node (ref "R23") (pin "2") (pinfunction "2_2") (pintype "passive"))
      (node (ref "U$1") (pin "VH") (pinfunction "HV_VH") (pintype "bidirectional"))
    )
    (net (code "174") (name "VCC") (class "Default")
      (node (ref "C9") (pin "1") (pinfunction "1_1") (pintype "passive"))
      (node (ref "U1") (pin "3") (pinfunction "VO_3") (pintype "power_in"))
      (node (ref "U2") (pin "13") (pinfunction "VREGIN_13") (pintype "input"))
    )
    (net (code "175") (name "VDD") (class "Default")
      (node (ref "C1") (pin "1") (pinfunction "1_1") (pintype "passive"))
      (node (ref "C2") (pin "1") (pinfunction "1_1") (pintype "passive"))
      (node (ref "C3") (pin "1") (pinfunction "1_1") (pintype "passive"))
      (node (ref "C4") (pin "1") (pinfunction "1_1") (pintype "passive"))
      (node (ref "C5") (pin "1") (pinfunction "1_1") (pintype "passive"))
      (node (ref "C6") (pin "1") (pinfunction "1_1") (pintype "passive"))
      (node (ref "C7") (pin "1") (pinfunction "1_1") (pintype "passive"))
      (node (ref "C8") (pin "1") (pinfunction "1_1") (pintype "passive"))
      (node (ref "J2") (pin "1") (pinfunction "1_1") (pintype "passive"))
      (node (ref "MUX0") (pin "24") (pinfunction "VDD_24") (pintype "power_in"))
      (node (ref "MUX1") (pin "21") (pinfunction "A0_21") (pintype "input"))
      (node (ref "MUX1") (pin "24") (pinfunction "VDD_24") (pintype "power_in"))
      (node (ref "MUX2") (pin "24") (pinfunction "VDD_24") (pintype "power_in"))
      (node (ref "MUX3") (pin "21") (pinfunction "A0_21") (pintype "input"))
      (node (ref "MUX3") (pin "24") (pinfunction "VDD_24") (pintype "power_in"))
      (node (ref "R15") (pin "2") (pinfunction "2_2") (pintype "passive"))
      (node (ref "R16") (pin "2") (pinfunction "2_2") (pintype "passive"))
      (node (ref "R21") (pin "2") (pinfunction "2_2") (pintype "passive"))
      (node (ref "R22") (pin "2") (pinfunction "2_2") (pintype "passive"))
      (node (ref "R26") (pin "2") (pinfunction "2_2") (pintype "passive"))
      (node (ref "R33") (pin "2") (pinfunction "2_2") (pintype "passive"))
      (node (ref "R37") (pin "2") (pinfunction "2_2") (pintype "passive"))
      (node (ref "R41") (pin "2") (pinfunction "2_2") (pintype "passive"))
      (node (ref "R45") (pin "2") (pinfunction "2_2") (pintype "passive"))
      (node (ref "R49") (pin "2") (pinfunction "2_2") (pintype "passive"))
      (node (ref "U2") (pin "22") (pinfunction "VDDA_22") (pintype "power_in"))
      (node (ref "U2") (pin "30") (pinfunction "VBAT_30") (pintype "power_in"))
      (node (ref "U2") (pin "40") (pinfunction "VDD_3_40") (pintype "power_in"))
      (node (ref "U2") (pin "48") (pinfunction "VDD_4_48") (pintype "power_in"))
      (node (ref "U2") (pin "61") (pinfunction "VDD_5_61") (pintype "power_in"))
      (node (ref "U2") (pin "75") (pinfunction "VDD_6_75") (pintype "power_in"))
      (node (ref "U2") (pin "8") (pinfunction "VDD_2_8") (pintype "power_in"))
      (node (ref "U2") (pin "89") (pinfunction "VDD_89") (pintype "power_in"))
      (node (ref "U4") (pin "3") (pinfunction "VO_3") (pintype "power_in"))
    )
    (net (code "176") (name "VREFH") (class "Default")
      (node (ref "U2") (pin "23") (pinfunction "VREFH_23") (pintype "power_in"))
    )
    (net (code "177") (name "VREFL") (class "Default")
      (node (ref "U2") (pin "24") (pinfunction "VREFL_24") (pintype "power_in"))
    )
    (net (code "178") (name "unconnected-(J2-Pad4)") (class "Default")
      (node (ref "J2") (pin "4") (pinfunction "4_4") (pintype "passive"))
    )
    (net (code "179") (name "unconnected-(J2-Pad5)") (class "Default")
      (node (ref "J2") (pin "5") (pinfunction "5_5") (pintype "passive"))
    )
    (net (code "180") (name "unconnected-(J2-Pad7)") (class "Default")
      (node (ref "J2") (pin "7") (pinfunction "7_7") (pintype "passive"))
    )
    (net (code "181") (name "unconnected-(MUX0-~{INT}-Pad1)") (class "Default")
      (node (ref "MUX0") (pin "1") (pinfunction "~{INT}_1") (pintype "output"))
    )
    (net (code "182") (name "unconnected-(MUX1-~{INT}-Pad1)") (class "Default")
      (node (ref "MUX1") (pin "1") (pinfunction "~{INT}_1") (pintype "output"))
    )
    (net (code "183") (name "unconnected-(MUX2-~{INT}-Pad1)") (class "Default")
      (node (ref "MUX2") (pin "1") (pinfunction "~{INT}_1") (pintype "output"))
    )
    (net (code "184") (name "unconnected-(MUX3-~{INT}-Pad1)") (class "Default")
      (node (ref "MUX3") (pin "1") (pinfunction "~{INT}_1") (pintype "output"))
    )
    (net (code "185") (name "unconnected-(U2-ADC0_DM1-Pad15)") (class "Default")
      (node (ref "U2") (pin "15") (pinfunction "ADC0_DM1_15") (pintype "bidirectional"))
    )
    (net (code "186") (name "unconnected-(U2-ADC0_DP1-Pad14)") (class "Default")
      (node (ref "U2") (pin "14") (pinfunction "ADC0_DP1_14") (pintype "bidirectional"))
    )
    (net (code "187") (name "unconnected-(U2-ADC1_DM1-Pad17)") (class "Default")
      (node (ref "U2") (pin "17") (pinfunction "ADC1_DM1_17") (pintype "bidirectional"))
    )
    (net (code "188") (name "unconnected-(U2-ADC1_DP1-Pad16)") (class "Default")
      (node (ref "U2") (pin "16") (pinfunction "ADC1_DP1_16") (pintype "bidirectional"))
    )
    (net (code "189") (name "unconnected-(U2-DAC0_OUT{slash}CMP1_IN3{slash}ADC0_SE23-Pad27)") (class "Default")
      (node (ref "U2") (pin "27") (pinfunction "DAC0_OUT/CMP1_IN3/ADC0_SE23_27") (pintype "bidirectional"))
    )
    (net (code "190") (name "unconnected-(U2-EXTAL32-Pad29)") (class "Default")
      (node (ref "U2") (pin "29") (pinfunction "EXTAL32_29") (pintype "passive"))
    )
    (net (code "191") (name "unconnected-(U2-PGA0_DM{slash}ADC0_DM0{slash}ADC1_DM3-Pad19)") (class "Default")
      (node (ref "U2") (pin "19") (pinfunction "PGA0_DM/ADC0_DM0/ADC1_DM3_19") (pintype "bidirectional"))
    )
    (net (code "192") (name "unconnected-(U2-PGA0_DP{slash}ADC0_DP0{slash}ADC1_DP3-Pad18)") (class "Default")
      (node (ref "U2") (pin "18") (pinfunction "PGA0_DP/ADC0_DP0/ADC1_DP3_18") (pintype "bidirectional"))
    )
    (net (code "193") (name "unconnected-(U2-PGA1_DM{slash}ADC1_DM0{slash}ADC0_DM3-Pad21)") (class "Default")
      (node (ref "U2") (pin "21") (pinfunction "PGA1_DM/ADC1_DM0/ADC0_DM3_21") (pintype "bidirectional"))
    )
    (net (code "194") (name "unconnected-(U2-PGA1_DP{slash}ADC1_DP0{slash}ADC0_DP3-Pad20)") (class "Default")
      (node (ref "U2") (pin "20") (pinfunction "PGA1_DP/ADC1_DP0/ADC0_DP3_20") (pintype "bidirectional"))
    )
    (net (code "195") (name "unconnected-(U2-PTA1-Pad35)") (class "Default")
      (node (ref "U2") (pin "35") (pinfunction "PTA1_35") (pintype "bidirectional"))
    )
    (net (code "196") (name "unconnected-(U2-PTA4{slash}LLWU_P3-Pad38)") (class "Default")
      (node (ref "U2") (pin "38") (pinfunction "PTA4/LLWU_P3_38") (pintype "bidirectional"))
    )
    (net (code "197") (name "unconnected-(U2-PTA5-Pad39)") (class "Default")
      (node (ref "U2") (pin "39") (pinfunction "PTA5_39") (pintype "bidirectional"))
    )
    (net (code "198") (name "unconnected-(U2-PTA12-Pad42)") (class "Default")
      (node (ref "U2") (pin "42") (pinfunction "PTA12_42") (pintype "bidirectional"))
    )
    (net (code "199") (name "unconnected-(U2-PTA13{slash}LLWU_P4-Pad43)") (class "Default")
      (node (ref "U2") (pin "43") (pinfunction "PTA13/LLWU_P4_43") (pintype "bidirectional"))
    )
    (net (code "200") (name "unconnected-(U2-PTA14-Pad44)") (class "Default")
      (node (ref "U2") (pin "44") (pinfunction "PTA14_44") (pintype "bidirectional"))
    )
    (net (code "201") (name "unconnected-(U2-PTA15-Pad45)") (class "Default")
      (node (ref "U2") (pin "45") (pinfunction "PTA15_45") (pintype "bidirectional"))
    )
    (net (code "202") (name "unconnected-(U2-PTA16-Pad46)") (class "Default")
      (node (ref "U2") (pin "46") (pinfunction "PTA16_46") (pintype "bidirectional"))
    )
    (net (code "203") (name "unconnected-(U2-PTA17-Pad47)") (class "Default")
      (node (ref "U2") (pin "47") (pinfunction "PTA17_47") (pintype "bidirectional"))
    )
    (net (code "204") (name "unconnected-(U2-PTA18-Pad50)") (class "Default")
      (node (ref "U2") (pin "50") (pinfunction "PTA18_50") (pintype "bidirectional"))
    )
    (net (code "205") (name "unconnected-(U2-PTA19-Pad51)") (class "Default")
      (node (ref "U2") (pin "51") (pinfunction "PTA19_51") (pintype "bidirectional"))
    )
    (net (code "206") (name "unconnected-(U2-PTB0{slash}LLWU_P5-Pad53)") (class "Default")
      (node (ref "U2") (pin "53") (pinfunction "PTB0/LLWU_P5_53") (pintype "bidirectional"))
    )
    (net (code "207") (name "unconnected-(U2-PTB1-Pad54)") (class "Default")
      (node (ref "U2") (pin "54") (pinfunction "PTB1_54") (pintype "bidirectional"))
    )
    (net (code "208") (name "unconnected-(U2-PTB9-Pad57)") (class "Default")
      (node (ref "U2") (pin "57") (pinfunction "PTB9_57") (pintype "bidirectional"))
    )
    (net (code "209") (name "unconnected-(U2-PTB10-Pad58)") (class "Default")
      (node (ref "U2") (pin "58") (pinfunction "PTB10_58") (pintype "bidirectional"))
    )
    (net (code "210") (name "unconnected-(U2-PTB11-Pad59)") (class "Default")
      (node (ref "U2") (pin "59") (pinfunction "PTB11_59") (pintype "bidirectional"))
    )
    (net (code "211") (name "unconnected-(U2-PTB16-Pad62)") (class "Default")
      (node (ref "U2") (pin "62") (pinfunction "PTB16_62") (pintype "bidirectional"))
    )
    (net (code "212") (name "unconnected-(U2-PTB17-Pad63)") (class "Default")
      (node (ref "U2") (pin "63") (pinfunction "PTB17_63") (pintype "bidirectional"))
    )
    (net (code "213") (name "unconnected-(U2-PTB18-Pad64)") (class "Default")
      (node (ref "U2") (pin "64") (pinfunction "PTB18_64") (pintype "bidirectional"))
    )
    (net (code "214") (name "unconnected-(U2-PTB19-Pad65)") (class "Default")
      (node (ref "U2") (pin "65") (pinfunction "PTB19_65") (pintype "bidirectional"))
    )
    (net (code "215") (name "unconnected-(U2-PTB20-Pad66)") (class "Default")
      (node (ref "U2") (pin "66") (pinfunction "PTB20_66") (pintype "bidirectional"))
    )
    (net (code "216") (name "unconnected-(U2-PTB21-Pad67)") (class "Default")
      (node (ref "U2") (pin "67") (pinfunction "PTB21_67") (pintype "bidirectional"))
    )
    (net (code "217") (name "unconnected-(U2-PTB22-Pad68)") (class "Default")
      (node (ref "U2") (pin "68") (pinfunction "PTB22_68") (pintype "bidirectional"))
    )
    (net (code "218") (name "unconnected-(U2-PTB23-Pad69)") (class "Default")
      (node (ref "U2") (pin "69") (pinfunction "PTB23_69") (pintype "bidirectional"))
    )
    (net (code "219") (name "unconnected-(U2-PTC0-Pad70)") (class "Default")
      (node (ref "U2") (pin "70") (pinfunction "PTC0_70") (pintype "bidirectional"))
    )
    (net (code "220") (name "unconnected-(U2-PTC1{slash}LLWU_P6-Pad71)") (class "Default")
      (node (ref "U2") (pin "71") (pinfunction "PTC1/LLWU_P6_71") (pintype "bidirectional"))
    )
    (net (code "221") (name "unconnected-(U2-PTC2-Pad72)") (class "Default")
      (node (ref "U2") (pin "72") (pinfunction "PTC2_72") (pintype "bidirectional"))
    )
    (net (code "222") (name "unconnected-(U2-PTC3{slash}LLWU_P7-Pad73)") (class "Default")
      (node (ref "U2") (pin "73") (pinfunction "PTC3/LLWU_P7_73") (pintype "bidirectional"))
    )
    (net (code "223") (name "unconnected-(U2-PTC4{slash}LLWU_P8-Pad76)") (class "Default")
      (node (ref "U2") (pin "76") (pinfunction "PTC4/LLWU_P8_76") (pintype "bidirectional"))
    )
    (net (code "224") (name "unconnected-(U2-PTC5{slash}LLWU_P9-Pad77)") (class "Default")
      (node (ref "U2") (pin "77") (pinfunction "PTC5/LLWU_P9_77") (pintype "bidirectional"))
    )
    (net (code "225") (name "unconnected-(U2-PTC6{slash}LLWU_P10-Pad78)") (class "Default")
      (node (ref "U2") (pin "78") (pinfunction "PTC6/LLWU_P10_78") (pintype "bidirectional"))
    )
    (net (code "226") (name "unconnected-(U2-PTC7-Pad79)") (class "Default")
      (node (ref "U2") (pin "79") (pinfunction "PTC7_79") (pintype "bidirectional"))
    )
    (net (code "227") (name "unconnected-(U2-PTC8-Pad80)") (class "Default")
      (node (ref "U2") (pin "80") (pinfunction "PTC8_80") (pintype "bidirectional"))
    )
    (net (code "228") (name "unconnected-(U2-PTC9-Pad81)") (class "Default")
      (node (ref "U2") (pin "81") (pinfunction "PTC9_81") (pintype "bidirectional"))
    )
    (net (code "229") (name "unconnected-(U2-PTC10-Pad82)") (class "Default")
      (node (ref "U2") (pin "82") (pinfunction "PTC10_82") (pintype "bidirectional"))
    )
    (net (code "230") (name "unconnected-(U2-PTC11{slash}LLWU_P11-Pad83)") (class "Default")
      (node (ref "U2") (pin "83") (pinfunction "PTC11/LLWU_P11_83") (pintype "bidirectional"))
    )
    (net (code "231") (name "unconnected-(U2-PTC12-Pad84)") (class "Default")
      (node (ref "U2") (pin "84") (pinfunction "PTC12_84") (pintype "bidirectional"))
    )
    (net (code "232") (name "unconnected-(U2-PTC13-Pad85)") (class "Default")
      (node (ref "U2") (pin "85") (pinfunction "PTC13_85") (pintype "bidirectional"))
    )
    (net (code "233") (name "unconnected-(U2-PTC14-Pad86)") (class "Default")
      (node (ref "U2") (pin "86") (pinfunction "PTC14_86") (pintype "bidirectional"))
    )
    (net (code "234") (name "unconnected-(U2-PTC15-Pad87)") (class "Default")
      (node (ref "U2") (pin "87") (pinfunction "PTC15_87") (pintype "bidirectional"))
    )
    (net (code "235") (name "unconnected-(U2-PTC17-Pad91)") (class "Default")
      (node (ref "U2") (pin "91") (pinfunction "PTC17_91") (pintype "bidirectional"))
    )
    (net (code "236") (name "unconnected-(U2-PTC18-Pad92)") (class "Default")
      (node (ref "U2") (pin "92") (pinfunction "PTC18_92") (pintype "bidirectional"))
    )
    (net (code "237") (name "unconnected-(U2-PTD0{slash}LLWU_P12-Pad93)") (class "Default")
      (node (ref "U2") (pin "93") (pinfunction "PTD0/LLWU_P12_93") (pintype "bidirectional"))
    )
    (net (code "238") (name "unconnected-(U2-PTD1-Pad94)") (class "Default")
      (node (ref "U2") (pin "94") (pinfunction "PTD1_94") (pintype "bidirectional"))
    )
    (net (code "239") (name "unconnected-(U2-PTD4{slash}LLWU_P14-Pad97)") (class "Default")
      (node (ref "U2") (pin "97") (pinfunction "PTD4/LLWU_P14_97") (pintype "bidirectional"))
    )
    (net (code "240") (name "unconnected-(U2-PTD5-Pad98)") (class "Default")
      (node (ref "U2") (pin "98") (pinfunction "PTD5_98") (pintype "bidirectional"))
    )
    (net (code "241") (name "unconnected-(U2-PTD6{slash}LLWU_P15-Pad99)") (class "Default")
      (node (ref "U2") (pin "99") (pinfunction "PTD6/LLWU_P15_99") (pintype "bidirectional"))
    )
    (net (code "242") (name "unconnected-(U2-PTD7-Pad100)") (class "Default")
      (node (ref "U2") (pin "100") (pinfunction "PTD7_100") (pintype "bidirectional"))
    )
    (net (code "243") (name "unconnected-(U2-PTE0-Pad1)") (class "Default")
      (node (ref "U2") (pin "1") (pinfunction "PTE0_1") (pintype "bidirectional"))
    )
    (net (code "244") (name "unconnected-(U2-PTE1{slash}LLWU_P0-Pad2)") (class "Default")
      (node (ref "U2") (pin "2") (pinfunction "PTE1/LLWU_P0_2") (pintype "bidirectional"))
    )
    (net (code "245") (name "unconnected-(U2-PTE2{slash}LLWU_P1-Pad3)") (class "Default")
      (node (ref "U2") (pin "3") (pinfunction "PTE2/LLWU_P1_3") (pintype "bidirectional"))
    )
    (net (code "246") (name "unconnected-(U2-PTE3-Pad4)") (class "Default")
      (node (ref "U2") (pin "4") (pinfunction "PTE3_4") (pintype "bidirectional"))
    )
    (net (code "247") (name "unconnected-(U2-PTE4{slash}LLWU_P2-Pad5)") (class "Default")
      (node (ref "U2") (pin "5") (pinfunction "PTE4/LLWU_P2_5") (pintype "bidirectional"))
    )
    (net (code "248") (name "unconnected-(U2-PTE24-Pad31)") (class "Default")
      (node (ref "U2") (pin "31") (pinfunction "PTE24_31") (pintype "bidirectional"))
    )
    (net (code "249") (name "unconnected-(U2-PTE25-Pad32)") (class "Default")
      (node (ref "U2") (pin "32") (pinfunction "PTE25_32") (pintype "bidirectional"))
    )
    (net (code "250") (name "unconnected-(U2-PTE26-Pad33)") (class "Default")
      (node (ref "U2") (pin "33") (pinfunction "PTE26_33") (pintype "bidirectional"))
    )
    (net (code "251") (name "unconnected-(U2-USB0_DM-Pad11)") (class "Default")
      (node (ref "U2") (pin "11") (pinfunction "USB0_DM_11") (pintype "passive"))
    )
    (net (code "252") (name "unconnected-(U2-USB0_DP-Pad10)") (class "Default")
      (node (ref "U2") (pin "10") (pinfunction "USB0_DP_10") (pintype "passive"))
    )
    (net (code "253") (name "unconnected-(U2-VOUT33-Pad12)") (class "Default")
      (node (ref "U2") (pin "12") (pinfunction "VOUT33_12") (pintype "output"))
    )
    (net (code "254") (name "unconnected-(U2-VREF_OUT{slash}CMP1_IN5{slash}CMP0_IN5{slash}ADC1_SE18-Pad26)") (class "Default")
      (node (ref "U2") (pin "26") (pinfunction "VREF_OUT/CMP1_IN5/CMP0_IN5/ADC1_SE18_26") (pintype "bidirectional"))
    )
    (net (code "255") (name "unconnected-(U2-XTAL32-Pad28)") (class "Default")
      (node (ref "U2") (pin "28") (pinfunction "XTAL32_28") (pintype "passive"))
    )
  )
)
